# DDR4_SDRAM.net
KiCad netlist of a schematic drawn in Altium Designer
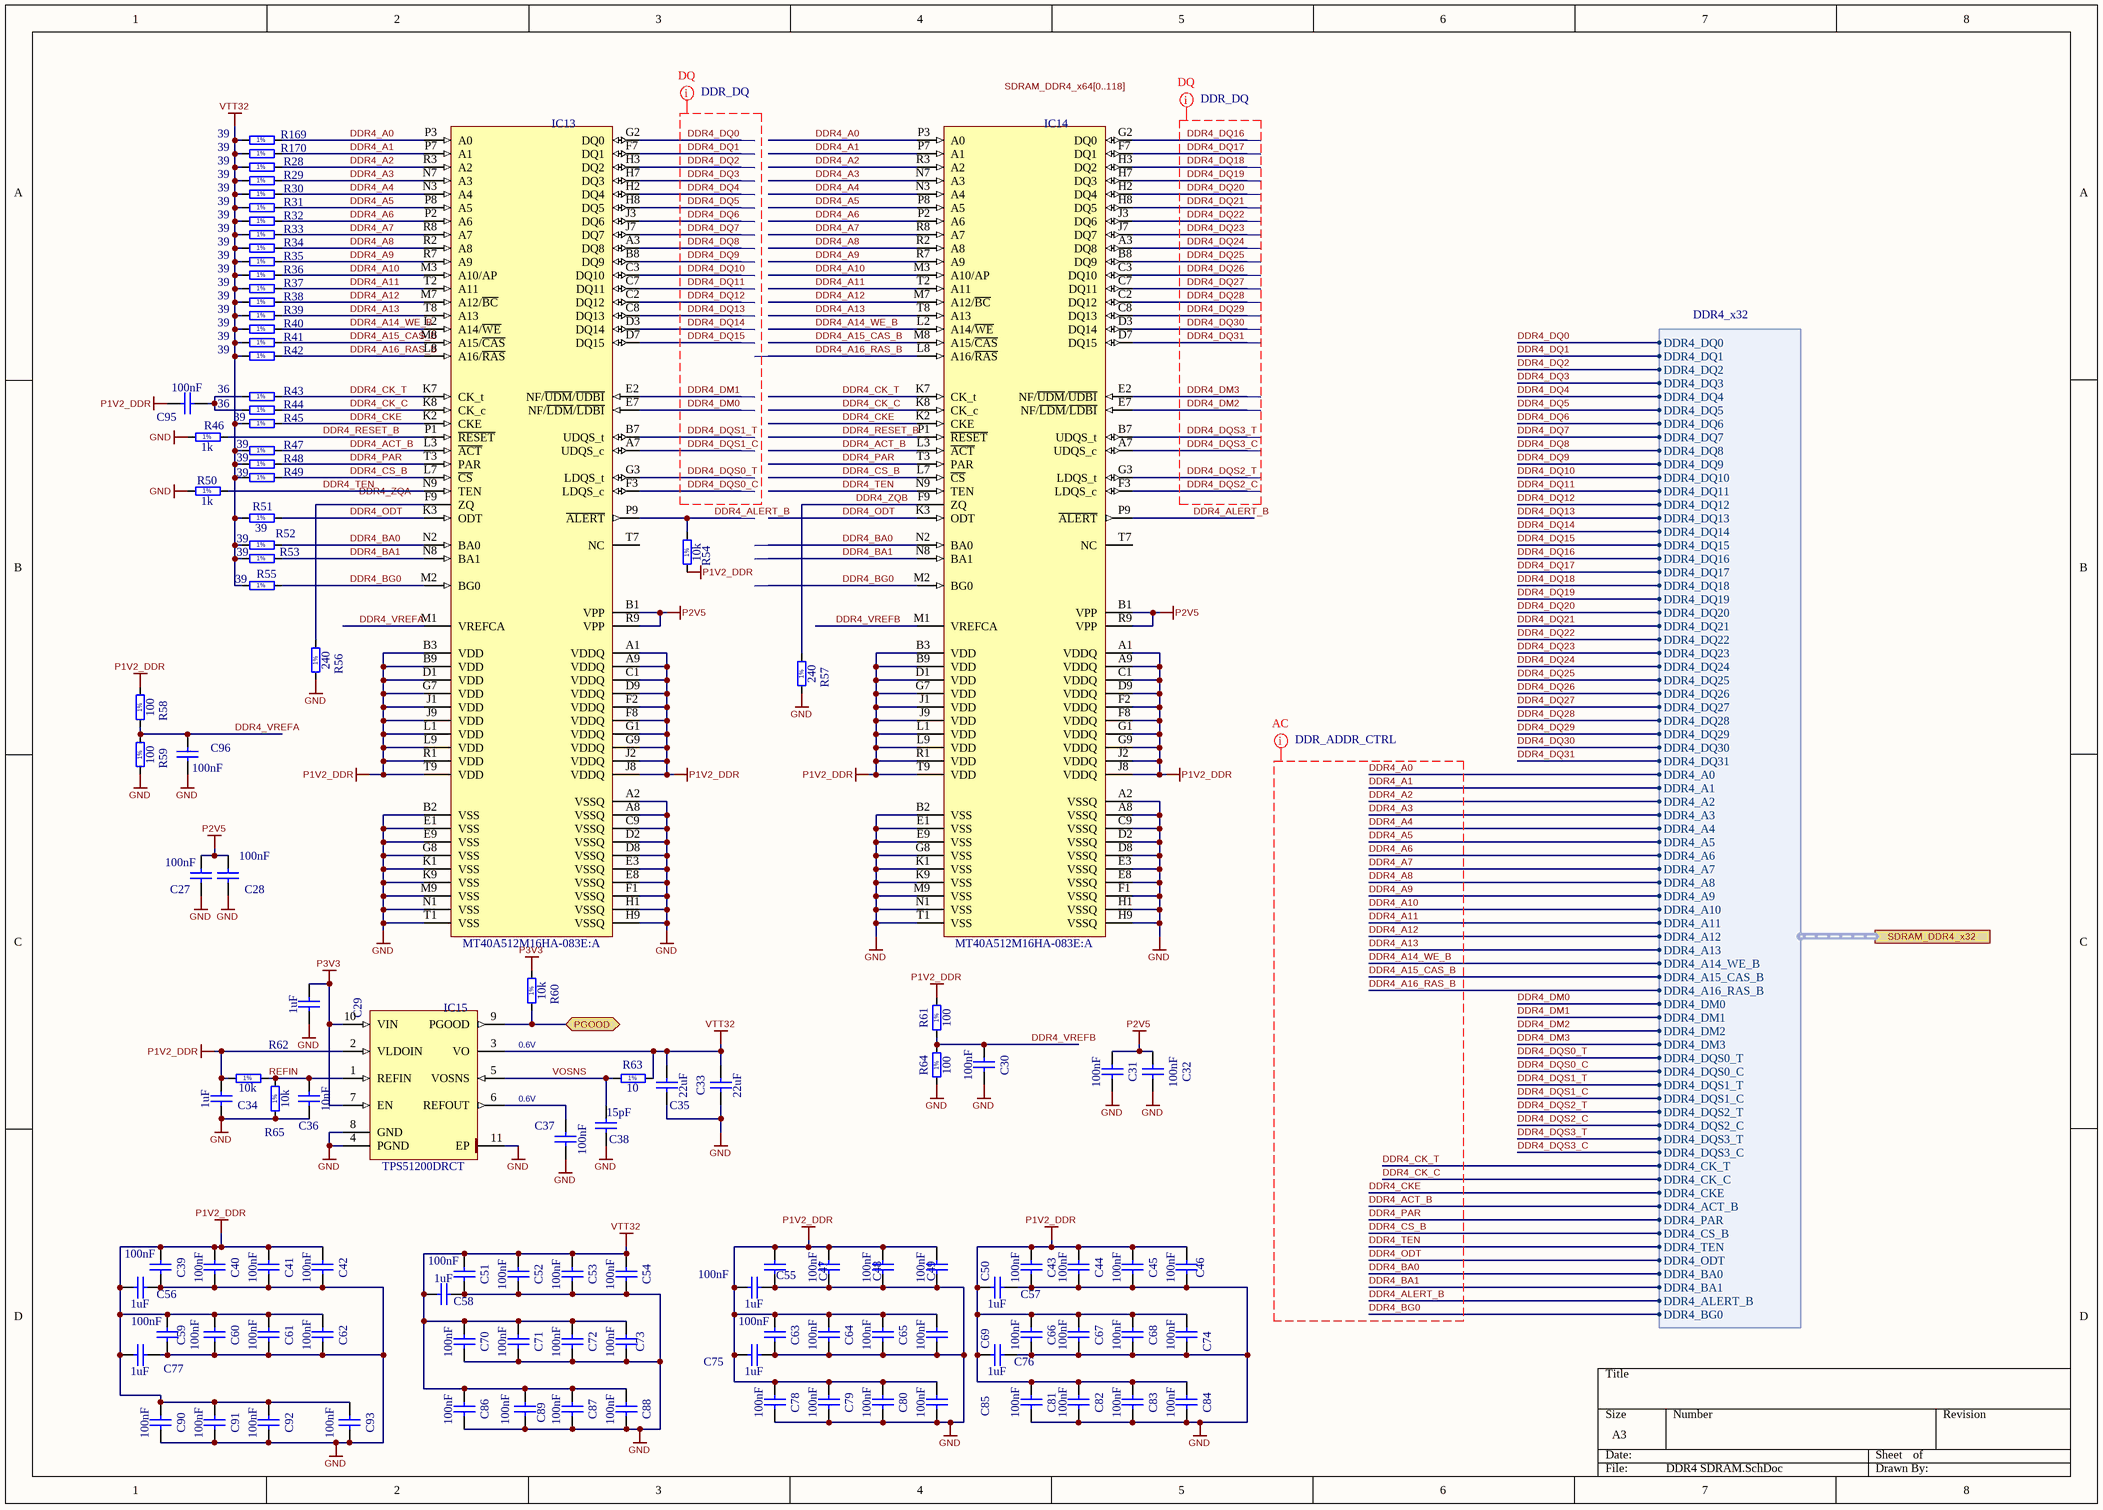
[diagram p0: DDR4 SDRAM.SchDoc]

(export (version "E")
  (design (tool "Eeschema 10.0.6"))
  (components
    (comp (ref "C27")
      (value "100nF")
      (footprint "CAPC0603X33N")
      (description "Non-polarised capacitor")
      (fields
        (field (name "MANUFACTURER PART NUMBER") "CC0201_100NF_6.3V_10%_X5R")
        (field (name "MANUFACTURER") "GENERIC")
        (field (name "AUTHOR") "CERN DEM JLC")
      )
      (libsource (lib "Capacitors") (part "Capacitor - non polarized"))
    )
    (comp (ref "C28")
      (value "100nF")
      (footprint "CAPC0603X33N")
      (description "Non-polarised capacitor")
      (fields
        (field (name "MANUFACTURER PART NUMBER") "CC0201_100NF_6.3V_10%_X5R")
        (field (name "MANUFACTURER") "GENERIC")
        (field (name "AUTHOR") "CERN DEM JLC")
      )
      (libsource (lib "Capacitors") (part "Capacitor - non polarized"))
    )
    (comp (ref "C29")
      (value "1uF")
      (footprint "CAPC1005X55N")
      (description "Non-polarised capacitor")
      (fields
        (field (name "MANUFACTURER PART NUMBER") "CC0402_1UF_16V_10%_X5R")
        (field (name "MANUFACTURER") "GENERIC")
        (field (name "AUTHOR") "CERN DEM JLC")
      )
      (libsource (lib "Capacitors") (part "Capacitor - non polarized"))
    )
    (comp (ref "C30")
      (value "100nF")
      (footprint "CAPC0603X33N")
      (description "Non-polarised capacitor")
      (fields
        (field (name "MANUFACTURER PART NUMBER") "CC0201_100NF_6.3V_10%_X5R")
        (field (name "MANUFACTURER") "GENERIC")
        (field (name "AUTHOR") "CERN DEM JLC")
      )
      (libsource (lib "Capacitors") (part "Capacitor - non polarized"))
    )
    (comp (ref "C31")
      (value "100nF")
      (footprint "CAPC0603X33N")
      (description "Non-polarised capacitor")
      (fields
        (field (name "MANUFACTURER PART NUMBER") "CC0201_100NF_6.3V_10%_X5R")
        (field (name "MANUFACTURER") "GENERIC")
        (field (name "AUTHOR") "CERN DEM JLC")
      )
      (libsource (lib "Capacitors") (part "Capacitor - non polarized"))
    )
    (comp (ref "C32")
      (value "100nF")
      (footprint "CAPC0603X33N")
      (description "Non-polarised capacitor")
      (fields
        (field (name "MANUFACTURER PART NUMBER") "CC0201_100NF_6.3V_10%_X5R")
        (field (name "MANUFACTURER") "GENERIC")
        (field (name "AUTHOR") "CERN DEM JLC")
      )
      (libsource (lib "Capacitors") (part "Capacitor - non polarized"))
    )
    (comp (ref "C33")
      (value "22uF")
      (footprint "CAPC2012X135N")
      (description "Non-polarised capacitor")
      (fields
        (field (name "MANUFACTURER PART NUMBER") "CC0805_22UF_10V_+80%-20%_Y5V")
        (field (name "MANUFACTURER") "GENERIC")
        (field (name "AUTHOR") "CERN DEM JLC")
      )
      (libsource (lib "Capacitors") (part "Capacitor - non polarized"))
    )
    (comp (ref "C34")
      (value "1uF")
      (footprint "CAPC1005X55N")
      (description "Non-polarised capacitor")
      (fields
        (field (name "MANUFACTURER PART NUMBER") "CC0402_1UF_16V_10%_X5R")
        (field (name "MANUFACTURER") "GENERIC")
        (field (name "AUTHOR") "CERN DEM JLC")
      )
      (libsource (lib "Capacitors") (part "Capacitor - non polarized"))
    )
    (comp (ref "C35")
      (value "22uF")
      (footprint "CAPC2012X135N")
      (description "Non-polarised capacitor")
      (fields
        (field (name "MANUFACTURER PART NUMBER") "CC0805_22UF_10V_+80%-20%_Y5V")
        (field (name "MANUFACTURER") "GENERIC")
        (field (name "AUTHOR") "CERN DEM JLC")
      )
      (libsource (lib "Capacitors") (part "Capacitor - non polarized"))
    )
    (comp (ref "C36")
      (value "10nF")
      (footprint "CAPC1005X55N")
      (description "Non-polarised capacitor")
      (fields
        (field (name "MANUFACTURER PART NUMBER") "CC0402_10NF_25V_10%_X7R")
        (field (name "MANUFACTURER") "GENERIC")
        (field (name "AUTHOR") "CERN DEM JLC")
      )
      (libsource (lib "Capacitors") (part "Capacitor - non polarized"))
    )
    (comp (ref "C37")
      (value "100nF")
      (footprint "CAPC0603X33N")
      (description "Non-polarised capacitor")
      (fields
        (field (name "MANUFACTURER PART NUMBER") "CC0201_100NF_6.3V_10%_X5R")
        (field (name "MANUFACTURER") "GENERIC")
        (field (name "AUTHOR") "CERN DEM JLC")
      )
      (libsource (lib "Capacitors") (part "Capacitor - non polarized"))
    )
    (comp (ref "C38")
      (value "15pF")
      (footprint "CAPC1005X55N")
      (description "Non-polarised capacitor")
      (fields
        (field (name "MANUFACTURER PART NUMBER") "CC0402_15PF_50V_5%_C0G")
        (field (name "MANUFACTURER") "GENERIC")
        (field (name "AUTHOR") "CERN DEM JLC")
      )
      (libsource (lib "Capacitors") (part "Capacitor - non polarized"))
    )
    (comp (ref "C39")
      (value "100nF")
      (footprint "CAPC0603X33N")
      (description "Non-polarised capacitor")
      (fields
        (field (name "MANUFACTURER PART NUMBER") "CC0201_100NF_6.3V_10%_X5R")
        (field (name "MANUFACTURER") "GENERIC")
        (field (name "AUTHOR") "CERN DEM JLC")
      )
      (libsource (lib "Capacitors") (part "Capacitor - non polarized"))
    )
    (comp (ref "C40")
      (value "100nF")
      (footprint "CAPC0603X33N")
      (description "Non-polarised capacitor")
      (fields
        (field (name "MANUFACTURER PART NUMBER") "CC0201_100NF_6.3V_10%_X5R")
        (field (name "MANUFACTURER") "GENERIC")
        (field (name "AUTHOR") "CERN DEM JLC")
      )
      (libsource (lib "Capacitors") (part "Capacitor - non polarized"))
    )
    (comp (ref "C41")
      (value "100nF")
      (footprint "CAPC0603X33N")
      (description "Non-polarised capacitor")
      (fields
        (field (name "MANUFACTURER PART NUMBER") "CC0201_100NF_6.3V_10%_X5R")
        (field (name "MANUFACTURER") "GENERIC")
        (field (name "AUTHOR") "CERN DEM JLC")
      )
      (libsource (lib "Capacitors") (part "Capacitor - non polarized"))
    )
    (comp (ref "C42")
      (value "100nF")
      (footprint "CAPC0603X33N")
      (description "Non-polarised capacitor")
      (fields
        (field (name "MANUFACTURER PART NUMBER") "CC0201_100NF_6.3V_10%_X5R")
        (field (name "MANUFACTURER") "GENERIC")
        (field (name "AUTHOR") "CERN DEM JLC")
      )
      (libsource (lib "Capacitors") (part "Capacitor - non polarized"))
    )
    (comp (ref "C43")
      (value "100nF")
      (footprint "CAPC0603X33N")
      (description "Non-polarised capacitor")
      (fields
        (field (name "MANUFACTURER PART NUMBER") "CC0201_100NF_6.3V_10%_X5R")
        (field (name "MANUFACTURER") "GENERIC")
        (field (name "AUTHOR") "CERN DEM JLC")
      )
      (libsource (lib "Capacitors") (part "Capacitor - non polarized"))
    )
    (comp (ref "C44")
      (value "100nF")
      (footprint "CAPC0603X33N")
      (description "Non-polarised capacitor")
      (fields
        (field (name "MANUFACTURER PART NUMBER") "CC0201_100NF_6.3V_10%_X5R")
        (field (name "MANUFACTURER") "GENERIC")
        (field (name "AUTHOR") "CERN DEM JLC")
      )
      (libsource (lib "Capacitors") (part "Capacitor - non polarized"))
    )
    (comp (ref "C45")
      (value "100nF")
      (footprint "CAPC0603X33N")
      (description "Non-polarised capacitor")
      (fields
        (field (name "MANUFACTURER PART NUMBER") "CC0201_100NF_6.3V_10%_X5R")
        (field (name "MANUFACTURER") "GENERIC")
        (field (name "AUTHOR") "CERN DEM JLC")
      )
      (libsource (lib "Capacitors") (part "Capacitor - non polarized"))
    )
    (comp (ref "C46")
      (value "100nF")
      (footprint "CAPC0603X33N")
      (description "Non-polarised capacitor")
      (fields
        (field (name "MANUFACTURER PART NUMBER") "CC0201_100NF_6.3V_10%_X5R")
        (field (name "MANUFACTURER") "GENERIC")
        (field (name "AUTHOR") "CERN DEM JLC")
      )
      (libsource (lib "Capacitors") (part "Capacitor - non polarized"))
    )
    (comp (ref "C47")
      (value "100nF")
      (footprint "CAPC0603X33N")
      (description "Non-polarised capacitor")
      (fields
        (field (name "MANUFACTURER PART NUMBER") "CC0201_100NF_6.3V_10%_X5R")
        (field (name "MANUFACTURER") "GENERIC")
        (field (name "AUTHOR") "CERN DEM JLC")
      )
      (libsource (lib "Capacitors") (part "Capacitor - non polarized"))
    )
    (comp (ref "C48")
      (value "100nF")
      (footprint "CAPC0603X33N")
      (description "Non-polarised capacitor")
      (fields
        (field (name "MANUFACTURER PART NUMBER") "CC0201_100NF_6.3V_10%_X5R")
        (field (name "MANUFACTURER") "GENERIC")
        (field (name "AUTHOR") "CERN DEM JLC")
      )
      (libsource (lib "Capacitors") (part "Capacitor - non polarized"))
    )
    (comp (ref "C49")
      (value "100nF")
      (footprint "CAPC0603X33N")
      (description "Non-polarised capacitor")
      (fields
        (field (name "MANUFACTURER PART NUMBER") "CC0201_100NF_6.3V_10%_X5R")
        (field (name "MANUFACTURER") "GENERIC")
        (field (name "AUTHOR") "CERN DEM JLC")
      )
      (libsource (lib "Capacitors") (part "Capacitor - non polarized"))
    )
    (comp (ref "C50")
      (value "100nF")
      (footprint "CAPC0603X33N")
      (description "Non-polarised capacitor")
      (fields
        (field (name "MANUFACTURER PART NUMBER") "CC0201_100NF_6.3V_10%_X5R")
        (field (name "MANUFACTURER") "GENERIC")
        (field (name "AUTHOR") "CERN DEM JLC")
      )
      (libsource (lib "Capacitors") (part "Capacitor - non polarized"))
    )
    (comp (ref "C51")
      (value "100nF")
      (footprint "CAPC0603X33N")
      (description "Non-polarised capacitor")
      (fields
        (field (name "MANUFACTURER PART NUMBER") "CC0201_100NF_6.3V_10%_X5R")
        (field (name "MANUFACTURER") "GENERIC")
        (field (name "AUTHOR") "CERN DEM JLC")
      )
      (libsource (lib "Capacitors") (part "Capacitor - non polarized"))
    )
    (comp (ref "C52")
      (value "100nF")
      (footprint "CAPC0603X33N")
      (description "Non-polarised capacitor")
      (fields
        (field (name "MANUFACTURER PART NUMBER") "CC0201_100NF_6.3V_10%_X5R")
        (field (name "MANUFACTURER") "GENERIC")
        (field (name "AUTHOR") "CERN DEM JLC")
      )
      (libsource (lib "Capacitors") (part "Capacitor - non polarized"))
    )
    (comp (ref "C53")
      (value "100nF")
      (footprint "CAPC0603X33N")
      (description "Non-polarised capacitor")
      (fields
        (field (name "MANUFACTURER PART NUMBER") "CC0201_100NF_6.3V_10%_X5R")
        (field (name "MANUFACTURER") "GENERIC")
        (field (name "AUTHOR") "CERN DEM JLC")
      )
      (libsource (lib "Capacitors") (part "Capacitor - non polarized"))
    )
    (comp (ref "C54")
      (value "100nF")
      (footprint "CAPC0603X33N")
      (description "Non-polarised capacitor")
      (fields
        (field (name "MANUFACTURER PART NUMBER") "CC0201_100NF_6.3V_10%_X5R")
        (field (name "MANUFACTURER") "GENERIC")
        (field (name "AUTHOR") "CERN DEM JLC")
      )
      (libsource (lib "Capacitors") (part "Capacitor - non polarized"))
    )
    (comp (ref "C55")
      (value "1uF")
      (footprint "CAPC1005X55N")
      (description "Non-polarised capacitor")
      (fields
        (field (name "MANUFACTURER PART NUMBER") "CC0402_1UF_16V_10%_X5R")
        (field (name "MANUFACTURER") "GENERIC")
        (field (name "AUTHOR") "CERN DEM JLC")
      )
      (libsource (lib "Capacitors") (part "Capacitor - non polarized"))
    )
    (comp (ref "C56")
      (value "1uF")
      (footprint "CAPC1005X55N")
      (description "Non-polarised capacitor")
      (fields
        (field (name "MANUFACTURER PART NUMBER") "CC0402_1UF_16V_10%_X5R")
        (field (name "MANUFACTURER") "GENERIC")
        (field (name "AUTHOR") "CERN DEM JLC")
      )
      (libsource (lib "Capacitors") (part "Capacitor - non polarized"))
    )
    (comp (ref "C57")
      (value "1uF")
      (footprint "CAPC1005X55N")
      (description "Non-polarised capacitor")
      (fields
        (field (name "MANUFACTURER PART NUMBER") "CC0402_1UF_16V_10%_X5R")
        (field (name "MANUFACTURER") "GENERIC")
        (field (name "AUTHOR") "CERN DEM JLC")
      )
      (libsource (lib "Capacitors") (part "Capacitor - non polarized"))
    )
    (comp (ref "C58")
      (value "1uF")
      (footprint "CAPC1005X55N")
      (description "Non-polarised capacitor")
      (fields
        (field (name "MANUFACTURER PART NUMBER") "CC0402_1UF_16V_10%_X5R")
        (field (name "MANUFACTURER") "GENERIC")
        (field (name "AUTHOR") "CERN DEM JLC")
      )
      (libsource (lib "Capacitors") (part "Capacitor - non polarized"))
    )
    (comp (ref "C59")
      (value "100nF")
      (footprint "CAPC0603X33N")
      (description "Non-polarised capacitor")
      (fields
        (field (name "MANUFACTURER PART NUMBER") "CC0201_100NF_6.3V_10%_X5R")
        (field (name "MANUFACTURER") "GENERIC")
        (field (name "AUTHOR") "CERN DEM JLC")
      )
      (libsource (lib "Capacitors") (part "Capacitor - non polarized"))
    )
    (comp (ref "C60")
      (value "100nF")
      (footprint "CAPC0603X33N")
      (description "Non-polarised capacitor")
      (fields
        (field (name "MANUFACTURER PART NUMBER") "CC0201_100NF_6.3V_10%_X5R")
        (field (name "MANUFACTURER") "GENERIC")
        (field (name "AUTHOR") "CERN DEM JLC")
      )
      (libsource (lib "Capacitors") (part "Capacitor - non polarized"))
    )
    (comp (ref "C61")
      (value "100nF")
      (footprint "CAPC0603X33N")
      (description "Non-polarised capacitor")
      (fields
        (field (name "MANUFACTURER PART NUMBER") "CC0201_100NF_6.3V_10%_X5R")
        (field (name "MANUFACTURER") "GENERIC")
        (field (name "AUTHOR") "CERN DEM JLC")
      )
      (libsource (lib "Capacitors") (part "Capacitor - non polarized"))
    )
    (comp (ref "C62")
      (value "100nF")
      (footprint "CAPC0603X33N")
      (description "Non-polarised capacitor")
      (fields
        (field (name "MANUFACTURER PART NUMBER") "CC0201_100NF_6.3V_10%_X5R")
        (field (name "MANUFACTURER") "GENERIC")
        (field (name "AUTHOR") "CERN DEM JLC")
      )
      (libsource (lib "Capacitors") (part "Capacitor - non polarized"))
    )
    (comp (ref "C63")
      (value "100nF")
      (footprint "CAPC0603X33N")
      (description "Non-polarised capacitor")
      (fields
        (field (name "MANUFACTURER PART NUMBER") "CC0201_100NF_6.3V_10%_X5R")
        (field (name "MANUFACTURER") "GENERIC")
        (field (name "AUTHOR") "CERN DEM JLC")
      )
      (libsource (lib "Capacitors") (part "Capacitor - non polarized"))
    )
    (comp (ref "C64")
      (value "100nF")
      (footprint "CAPC0603X33N")
      (description "Non-polarised capacitor")
      (fields
        (field (name "MANUFACTURER PART NUMBER") "CC0201_100NF_6.3V_10%_X5R")
        (field (name "MANUFACTURER") "GENERIC")
        (field (name "AUTHOR") "CERN DEM JLC")
      )
      (libsource (lib "Capacitors") (part "Capacitor - non polarized"))
    )
    (comp (ref "C65")
      (value "100nF")
      (footprint "CAPC0603X33N")
      (description "Non-polarised capacitor")
      (fields
        (field (name "MANUFACTURER PART NUMBER") "CC0201_100NF_6.3V_10%_X5R")
        (field (name "MANUFACTURER") "GENERIC")
        (field (name "AUTHOR") "CERN DEM JLC")
      )
      (libsource (lib "Capacitors") (part "Capacitor - non polarized"))
    )
    (comp (ref "C66")
      (value "100nF")
      (footprint "CAPC0603X33N")
      (description "Non-polarised capacitor")
      (fields
        (field (name "MANUFACTURER PART NUMBER") "CC0201_100NF_6.3V_10%_X5R")
        (field (name "MANUFACTURER") "GENERIC")
        (field (name "AUTHOR") "CERN DEM JLC")
      )
      (libsource (lib "Capacitors") (part "Capacitor - non polarized"))
    )
    (comp (ref "C67")
      (value "100nF")
      (footprint "CAPC0603X33N")
      (description "Non-polarised capacitor")
      (fields
        (field (name "MANUFACTURER PART NUMBER") "CC0201_100NF_6.3V_10%_X5R")
        (field (name "MANUFACTURER") "GENERIC")
        (field (name "AUTHOR") "CERN DEM JLC")
      )
      (libsource (lib "Capacitors") (part "Capacitor - non polarized"))
    )
    (comp (ref "C68")
      (value "100nF")
      (footprint "CAPC0603X33N")
      (description "Non-polarised capacitor")
      (fields
        (field (name "MANUFACTURER PART NUMBER") "CC0201_100NF_6.3V_10%_X5R")
        (field (name "MANUFACTURER") "GENERIC")
        (field (name "AUTHOR") "CERN DEM JLC")
      )
      (libsource (lib "Capacitors") (part "Capacitor - non polarized"))
    )
    (comp (ref "C69")
      (value "100nF")
      (footprint "CAPC0603X33N")
      (description "Non-polarised capacitor")
      (fields
        (field (name "MANUFACTURER PART NUMBER") "CC0201_100NF_6.3V_10%_X5R")
        (field (name "MANUFACTURER") "GENERIC")
        (field (name "AUTHOR") "CERN DEM JLC")
      )
      (libsource (lib "Capacitors") (part "Capacitor - non polarized"))
    )
    (comp (ref "C70")
      (value "100nF")
      (footprint "CAPC0603X33N")
      (description "Non-polarised capacitor")
      (fields
        (field (name "MANUFACTURER PART NUMBER") "CC0201_100NF_6.3V_10%_X5R")
        (field (name "MANUFACTURER") "GENERIC")
        (field (name "AUTHOR") "CERN DEM JLC")
      )
      (libsource (lib "Capacitors") (part "Capacitor - non polarized"))
    )
    (comp (ref "C71")
      (value "100nF")
      (footprint "CAPC0603X33N")
      (description "Non-polarised capacitor")
      (fields
        (field (name "MANUFACTURER PART NUMBER") "CC0201_100NF_6.3V_10%_X5R")
        (field (name "MANUFACTURER") "GENERIC")
        (field (name "AUTHOR") "CERN DEM JLC")
      )
      (libsource (lib "Capacitors") (part "Capacitor - non polarized"))
    )
    (comp (ref "C72")
      (value "100nF")
      (footprint "CAPC0603X33N")
      (description "Non-polarised capacitor")
      (fields
        (field (name "MANUFACTURER PART NUMBER") "CC0201_100NF_6.3V_10%_X5R")
        (field (name "MANUFACTURER") "GENERIC")
        (field (name "AUTHOR") "CERN DEM JLC")
      )
      (libsource (lib "Capacitors") (part "Capacitor - non polarized"))
    )
    (comp (ref "C73")
      (value "100nF")
      (footprint "CAPC0603X33N")
      (description "Non-polarised capacitor")
      (fields
        (field (name "MANUFACTURER PART NUMBER") "CC0201_100NF_6.3V_10%_X5R")
        (field (name "MANUFACTURER") "GENERIC")
        (field (name "AUTHOR") "CERN DEM JLC")
      )
      (libsource (lib "Capacitors") (part "Capacitor - non polarized"))
    )
    (comp (ref "C74")
      (value "100nF")
      (footprint "CAPC0603X33N")
      (description "Non-polarised capacitor")
      (fields
        (field (name "MANUFACTURER PART NUMBER") "CC0201_100NF_6.3V_10%_X5R")
        (field (name "MANUFACTURER") "GENERIC")
        (field (name "AUTHOR") "CERN DEM JLC")
      )
      (libsource (lib "Capacitors") (part "Capacitor - non polarized"))
    )
    (comp (ref "C75")
      (value "1uF")
      (footprint "CAPC1005X55N")
      (description "Non-polarised capacitor")
      (fields
        (field (name "MANUFACTURER PART NUMBER") "CC0402_1UF_16V_10%_X5R")
        (field (name "MANUFACTURER") "GENERIC")
        (field (name "AUTHOR") "CERN DEM JLC")
      )
      (libsource (lib "Capacitors") (part "Capacitor - non polarized"))
    )
    (comp (ref "C76")
      (value "1uF")
      (footprint "CAPC1005X55N")
      (description "Non-polarised capacitor")
      (fields
        (field (name "MANUFACTURER PART NUMBER") "CC0402_1UF_16V_10%_X5R")
        (field (name "MANUFACTURER") "GENERIC")
        (field (name "AUTHOR") "CERN DEM JLC")
      )
      (libsource (lib "Capacitors") (part "Capacitor - non polarized"))
    )
    (comp (ref "C77")
      (value "1uF")
      (footprint "CAPC1005X55N")
      (description "Non-polarised capacitor")
      (fields
        (field (name "MANUFACTURER PART NUMBER") "CC0402_1UF_16V_10%_X5R")
        (field (name "MANUFACTURER") "GENERIC")
        (field (name "AUTHOR") "CERN DEM JLC")
      )
      (libsource (lib "Capacitors") (part "Capacitor - non polarized"))
    )
    (comp (ref "C78")
      (value "100nF")
      (footprint "CAPC0603X33N")
      (description "Non-polarised capacitor")
      (fields
        (field (name "MANUFACTURER PART NUMBER") "CC0201_100NF_6.3V_10%_X5R")
        (field (name "MANUFACTURER") "GENERIC")
        (field (name "AUTHOR") "CERN DEM JLC")
      )
      (libsource (lib "Capacitors") (part "Capacitor - non polarized"))
    )
    (comp (ref "C79")
      (value "100nF")
      (footprint "CAPC0603X33N")
      (description "Non-polarised capacitor")
      (fields
        (field (name "MANUFACTURER PART NUMBER") "CC0201_100NF_6.3V_10%_X5R")
        (field (name "MANUFACTURER") "GENERIC")
        (field (name "AUTHOR") "CERN DEM JLC")
      )
      (libsource (lib "Capacitors") (part "Capacitor - non polarized"))
    )
    (comp (ref "C80")
      (value "100nF")
      (footprint "CAPC0603X33N")
      (description "Non-polarised capacitor")
      (fields
        (field (name "MANUFACTURER PART NUMBER") "CC0201_100NF_6.3V_10%_X5R")
        (field (name "MANUFACTURER") "GENERIC")
        (field (name "AUTHOR") "CERN DEM JLC")
      )
      (libsource (lib "Capacitors") (part "Capacitor - non polarized"))
    )
    (comp (ref "C81")
      (value "100nF")
      (footprint "CAPC0603X33N")
      (description "Non-polarised capacitor")
      (fields
        (field (name "MANUFACTURER PART NUMBER") "CC0201_100NF_6.3V_10%_X5R")
        (field (name "MANUFACTURER") "GENERIC")
        (field (name "AUTHOR") "CERN DEM JLC")
      )
      (libsource (lib "Capacitors") (part "Capacitor - non polarized"))
    )
    (comp (ref "C82")
      (value "100nF")
      (footprint "CAPC0603X33N")
      (description "Non-polarised capacitor")
      (fields
        (field (name "MANUFACTURER PART NUMBER") "CC0201_100NF_6.3V_10%_X5R")
        (field (name "MANUFACTURER") "GENERIC")
        (field (name "AUTHOR") "CERN DEM JLC")
      )
      (libsource (lib "Capacitors") (part "Capacitor - non polarized"))
    )
    (comp (ref "C83")
      (value "100nF")
      (footprint "CAPC0603X33N")
      (description "Non-polarised capacitor")
      (fields
        (field (name "MANUFACTURER PART NUMBER") "CC0201_100NF_6.3V_10%_X5R")
        (field (name "MANUFACTURER") "GENERIC")
        (field (name "AUTHOR") "CERN DEM JLC")
      )
      (libsource (lib "Capacitors") (part "Capacitor - non polarized"))
    )
    (comp (ref "C84")
      (value "100nF")
      (footprint "CAPC0603X33N")
      (description "Non-polarised capacitor")
      (fields
        (field (name "MANUFACTURER PART NUMBER") "CC0201_100NF_6.3V_10%_X5R")
        (field (name "MANUFACTURER") "GENERIC")
        (field (name "AUTHOR") "CERN DEM JLC")
      )
      (libsource (lib "Capacitors") (part "Capacitor - non polarized"))
    )
    (comp (ref "C85")
      (value "100nF")
      (footprint "CAPC0603X33N")
      (description "Non-polarised capacitor")
      (fields
        (field (name "MANUFACTURER PART NUMBER") "CC0201_100NF_6.3V_10%_X5R")
        (field (name "MANUFACTURER") "GENERIC")
        (field (name "AUTHOR") "CERN DEM JLC")
      )
      (libsource (lib "Capacitors") (part "Capacitor - non polarized"))
    )
    (comp (ref "C86")
      (value "100nF")
      (footprint "CAPC0603X33N")
      (description "Non-polarised capacitor")
      (fields
        (field (name "MANUFACTURER PART NUMBER") "CC0201_100NF_6.3V_10%_X5R")
        (field (name "MANUFACTURER") "GENERIC")
        (field (name "AUTHOR") "CERN DEM JLC")
      )
      (libsource (lib "Capacitors") (part "Capacitor - non polarized"))
    )
    (comp (ref "C87")
      (value "100nF")
      (footprint "CAPC0603X33N")
      (description "Non-polarised capacitor")
      (fields
        (field (name "MANUFACTURER PART NUMBER") "CC0201_100NF_6.3V_10%_X5R")
        (field (name "MANUFACTURER") "GENERIC")
        (field (name "AUTHOR") "CERN DEM JLC")
      )
      (libsource (lib "Capacitors") (part "Capacitor - non polarized"))
    )
    (comp (ref "C88")
      (value "100nF")
      (footprint "CAPC0603X33N")
      (description "Non-polarised capacitor")
      (fields
        (field (name "MANUFACTURER PART NUMBER") "CC0201_100NF_6.3V_10%_X5R")
        (field (name "MANUFACTURER") "GENERIC")
        (field (name "AUTHOR") "CERN DEM JLC")
      )
      (libsource (lib "Capacitors") (part "Capacitor - non polarized"))
    )
    (comp (ref "C89")
      (value "100nF")
      (footprint "CAPC0603X33N")
      (description "Non-polarised capacitor")
      (fields
        (field (name "MANUFACTURER PART NUMBER") "CC0201_100NF_6.3V_10%_X5R")
        (field (name "MANUFACTURER") "GENERIC")
        (field (name "AUTHOR") "CERN DEM JLC")
      )
      (libsource (lib "Capacitors") (part "Capacitor - non polarized"))
    )
    (comp (ref "C90")
      (value "100nF")
      (footprint "CAPC0603X33N")
      (description "Non-polarised capacitor")
      (fields
        (field (name "MANUFACTURER PART NUMBER") "CC0201_100NF_6.3V_10%_X5R")
        (field (name "MANUFACTURER") "GENERIC")
        (field (name "AUTHOR") "CERN DEM JLC")
      )
      (libsource (lib "Capacitors") (part "Capacitor - non polarized"))
    )
    (comp (ref "C91")
      (value "100nF")
      (footprint "CAPC0603X33N")
      (description "Non-polarised capacitor")
      (fields
        (field (name "MANUFACTURER PART NUMBER") "CC0201_100NF_6.3V_10%_X5R")
        (field (name "MANUFACTURER") "GENERIC")
        (field (name "AUTHOR") "CERN DEM JLC")
      )
      (libsource (lib "Capacitors") (part "Capacitor - non polarized"))
    )
    (comp (ref "C92")
      (value "100nF")
      (footprint "CAPC0603X33N")
      (description "Non-polarised capacitor")
      (fields
        (field (name "MANUFACTURER PART NUMBER") "CC0201_100NF_6.3V_10%_X5R")
        (field (name "MANUFACTURER") "GENERIC")
        (field (name "AUTHOR") "CERN DEM JLC")
      )
      (libsource (lib "Capacitors") (part "Capacitor - non polarized"))
    )
    (comp (ref "C93")
      (value "100nF")
      (footprint "CAPC0603X33N")
      (description "Non-polarised capacitor")
      (fields
        (field (name "MANUFACTURER PART NUMBER") "CC0201_100NF_6.3V_10%_X5R")
        (field (name "MANUFACTURER") "GENERIC")
        (field (name "AUTHOR") "CERN DEM JLC")
      )
      (libsource (lib "Capacitors") (part "Capacitor - non polarized"))
    )
    (comp (ref "C95")
      (value "100nF")
      (footprint "CAPC0603X33N")
      (description "Non-polarised capacitor")
      (fields
        (field (name "MANUFACTURER PART NUMBER") "CC0201_100NF_6.3V_10%_X5R")
        (field (name "MANUFACTURER") "GENERIC")
        (field (name "AUTHOR") "CERN DEM JLC")
      )
      (libsource (lib "Capacitors") (part "Capacitor - non polarized"))
    )
    (comp (ref "C96")
      (value "100nF")
      (footprint "CAPC0603X33N")
      (description "Non-polarised capacitor")
      (fields
        (field (name "MANUFACTURER PART NUMBER") "CC0201_100NF_6.3V_10%_X5R")
        (field (name "MANUFACTURER") "GENERIC")
        (field (name "AUTHOR") "CERN DEM JLC")
      )
      (libsource (lib "Capacitors") (part "Capacitor - non polarized"))
    )
    (comp (ref "IC13")
      (value "MT40A512M16HA-083E:A")
      (footprint "BGA96C80P9X16_900X1400X120")
      (description "+1.2V, 8Gb (512 Meg x 16 x 8 Banks) DDR4 SDRAM")
      (fields (field (name "MANUFACTURER") "MICRON TECHNOLOGY") (field (name "AUTHOR") "CERN DEM MR"))
      (libsource (lib "ICs And Semiconductors") (part "MT40A512M16HA"))
    )
    (comp (ref "IC14")
      (value "MT40A512M16HA-083E:A")
      (footprint "BGA96C80P9X16_900X1400X120")
      (description "+1.2V, 8Gb (512 Meg x 16 x 8 Banks) DDR4 SDRAM")
      (fields (field (name "MANUFACTURER") "MICRON TECHNOLOGY") (field (name "AUTHOR") "CERN DEM MR"))
      (libsource (lib "ICs And Semiconductors") (part "MT40A512M16HA"))
    )
    (comp (ref "IC15")
      (value "TPS51200DRCT")
      (footprint "TEXAS_DRC (S-PVSON-N10)")
      (description "Sink/Source DDR Termination Regulator")
      (fields (field (name "MANUFACTURER") "TEXAS INSTRUMENTS") (field (name "AUTHOR") "CERN DEM JLC"))
      (libsource (lib "ICs And Semiconductors") (part "TPS51200DRC"))
    )
    (comp (ref "R28")
      (value "39")
      (footprint "RESC1005X40N")
      (description "Resistor - 1%")
      (fields
        (field (name "MANUFACTURER PART NUMBER") "R0402_39R_1%_0.0625W_100PPM")
        (field (name "MANUFACTURER") "GENERIC")
        (field (name "AUTHOR") "CERN DEM JLC")
      )
      (libsource (lib "Resistors") (part "Resistor - 1%"))
    )
    (comp (ref "R29")
      (value "39")
      (footprint "RESC1005X40N")
      (description "Resistor - 1%")
      (fields
        (field (name "MANUFACTURER PART NUMBER") "R0402_39R_1%_0.0625W_100PPM")
        (field (name "MANUFACTURER") "GENERIC")
        (field (name "AUTHOR") "CERN DEM JLC")
      )
      (libsource (lib "Resistors") (part "Resistor - 1%"))
    )
    (comp (ref "R30")
      (value "39")
      (footprint "RESC1005X40N")
      (description "Resistor - 1%")
      (fields
        (field (name "MANUFACTURER PART NUMBER") "R0402_39R_1%_0.0625W_100PPM")
        (field (name "MANUFACTURER") "GENERIC")
        (field (name "AUTHOR") "CERN DEM JLC")
      )
      (libsource (lib "Resistors") (part "Resistor - 1%"))
    )
    (comp (ref "R31")
      (value "39")
      (footprint "RESC1005X40N")
      (description "Resistor - 1%")
      (fields
        (field (name "MANUFACTURER PART NUMBER") "R0402_39R_1%_0.0625W_100PPM")
        (field (name "MANUFACTURER") "GENERIC")
        (field (name "AUTHOR") "CERN DEM JLC")
      )
      (libsource (lib "Resistors") (part "Resistor - 1%"))
    )
    (comp (ref "R32")
      (value "39")
      (footprint "RESC1005X40N")
      (description "Resistor - 1%")
      (fields
        (field (name "MANUFACTURER PART NUMBER") "R0402_39R_1%_0.0625W_100PPM")
        (field (name "MANUFACTURER") "GENERIC")
        (field (name "AUTHOR") "CERN DEM JLC")
      )
      (libsource (lib "Resistors") (part "Resistor - 1%"))
    )
    (comp (ref "R33")
      (value "39")
      (footprint "RESC1005X40N")
      (description "Resistor - 1%")
      (fields
        (field (name "MANUFACTURER PART NUMBER") "R0402_39R_1%_0.0625W_100PPM")
        (field (name "MANUFACTURER") "GENERIC")
        (field (name "AUTHOR") "CERN DEM JLC")
      )
      (libsource (lib "Resistors") (part "Resistor - 1%"))
    )
    (comp (ref "R34")
      (value "39")
      (footprint "RESC1005X40N")
      (description "Resistor - 1%")
      (fields
        (field (name "MANUFACTURER PART NUMBER") "R0402_39R_1%_0.0625W_100PPM")
        (field (name "MANUFACTURER") "GENERIC")
        (field (name "AUTHOR") "CERN DEM JLC")
      )
      (libsource (lib "Resistors") (part "Resistor - 1%"))
    )
    (comp (ref "R35")
      (value "39")
      (footprint "RESC1005X40N")
      (description "Resistor - 1%")
      (fields
        (field (name "MANUFACTURER PART NUMBER") "R0402_39R_1%_0.0625W_100PPM")
        (field (name "MANUFACTURER") "GENERIC")
        (field (name "AUTHOR") "CERN DEM JLC")
      )
      (libsource (lib "Resistors") (part "Resistor - 1%"))
    )
    (comp (ref "R36")
      (value "39")
      (footprint "RESC1005X40N")
      (description "Resistor - 1%")
      (fields
        (field (name "MANUFACTURER PART NUMBER") "R0402_39R_1%_0.0625W_100PPM")
        (field (name "MANUFACTURER") "GENERIC")
        (field (name "AUTHOR") "CERN DEM JLC")
      )
      (libsource (lib "Resistors") (part "Resistor - 1%"))
    )
    (comp (ref "R37")
      (value "39")
      (footprint "RESC1005X40N")
      (description "Resistor - 1%")
      (fields
        (field (name "MANUFACTURER PART NUMBER") "R0402_39R_1%_0.0625W_100PPM")
        (field (name "MANUFACTURER") "GENERIC")
        (field (name "AUTHOR") "CERN DEM JLC")
      )
      (libsource (lib "Resistors") (part "Resistor - 1%"))
    )
    (comp (ref "R38")
      (value "39")
      (footprint "RESC1005X40N")
      (description "Resistor - 1%")
      (fields
        (field (name "MANUFACTURER PART NUMBER") "R0402_39R_1%_0.0625W_100PPM")
        (field (name "MANUFACTURER") "GENERIC")
        (field (name "AUTHOR") "CERN DEM JLC")
      )
      (libsource (lib "Resistors") (part "Resistor - 1%"))
    )
    (comp (ref "R39")
      (value "39")
      (footprint "RESC1005X40N")
      (description "Resistor - 1%")
      (fields
        (field (name "MANUFACTURER PART NUMBER") "R0402_39R_1%_0.0625W_100PPM")
        (field (name "MANUFACTURER") "GENERIC")
        (field (name "AUTHOR") "CERN DEM JLC")
      )
      (libsource (lib "Resistors") (part "Resistor - 1%"))
    )
    (comp (ref "R40")
      (value "39")
      (footprint "RESC1005X40N")
      (description "Resistor - 1%")
      (fields
        (field (name "MANUFACTURER PART NUMBER") "R0402_39R_1%_0.0625W_100PPM")
        (field (name "MANUFACTURER") "GENERIC")
        (field (name "AUTHOR") "CERN DEM JLC")
      )
      (libsource (lib "Resistors") (part "Resistor - 1%"))
    )
    (comp (ref "R41")
      (value "39")
      (footprint "RESC1005X40N")
      (description "Resistor - 1%")
      (fields
        (field (name "MANUFACTURER PART NUMBER") "R0402_39R_1%_0.0625W_100PPM")
        (field (name "MANUFACTURER") "GENERIC")
        (field (name "AUTHOR") "CERN DEM JLC")
      )
      (libsource (lib "Resistors") (part "Resistor - 1%"))
    )
    (comp (ref "R42")
      (value "39")
      (footprint "RESC1005X40N")
      (description "Resistor - 1%")
      (fields
        (field (name "MANUFACTURER PART NUMBER") "R0402_39R_1%_0.0625W_100PPM")
        (field (name "MANUFACTURER") "GENERIC")
        (field (name "AUTHOR") "CERN DEM JLC")
      )
      (libsource (lib "Resistors") (part "Resistor - 1%"))
    )
    (comp (ref "R43")
      (value "36")
      (footprint "RESC1005X40N")
      (description "Resistor - 1%")
      (fields
        (field (name "MANUFACTURER PART NUMBER") "R0402_36R_1%_0.0625W_100PPM")
        (field (name "MANUFACTURER") "GENERIC")
        (field (name "AUTHOR") "CERN DEM JLC")
      )
      (libsource (lib "Resistors") (part "Resistor - 1%"))
    )
    (comp (ref "R44")
      (value "36")
      (footprint "RESC1005X40N")
      (description "Resistor - 1%")
      (fields
        (field (name "MANUFACTURER PART NUMBER") "R0402_36R_1%_0.0625W_100PPM")
        (field (name "MANUFACTURER") "GENERIC")
        (field (name "AUTHOR") "CERN DEM JLC")
      )
      (libsource (lib "Resistors") (part "Resistor - 1%"))
    )
    (comp (ref "R45")
      (value "39")
      (footprint "RESC1005X40N")
      (description "Resistor - 1%")
      (fields
        (field (name "MANUFACTURER PART NUMBER") "R0402_39R_1%_0.0625W_100PPM")
        (field (name "MANUFACTURER") "GENERIC")
        (field (name "AUTHOR") "CERN DEM JLC")
      )
      (libsource (lib "Resistors") (part "Resistor - 1%"))
    )
    (comp (ref "R46")
      (value "1k")
      (footprint "RESC1005X40N")
      (description "Resistor - 1%")
      (fields
        (field (name "MANUFACTURER PART NUMBER") "R0402_1K_1%_0.0625W_100PPM")
        (field (name "MANUFACTURER") "GENERIC")
        (field (name "AUTHOR") "CERN DEM JLC")
      )
      (libsource (lib "Resistors") (part "Resistor - 1%"))
    )
    (comp (ref "R47")
      (value "39")
      (footprint "RESC1005X40N")
      (description "Resistor - 1%")
      (fields
        (field (name "MANUFACTURER PART NUMBER") "R0402_39R_1%_0.0625W_100PPM")
        (field (name "MANUFACTURER") "GENERIC")
        (field (name "AUTHOR") "CERN DEM JLC")
      )
      (libsource (lib "Resistors") (part "Resistor - 1%"))
    )
    (comp (ref "R48")
      (value "39")
      (footprint "RESC1005X40N")
      (description "Resistor - 1%")
      (fields
        (field (name "MANUFACTURER PART NUMBER") "R0402_39R_1%_0.0625W_100PPM")
        (field (name "MANUFACTURER") "GENERIC")
        (field (name "AUTHOR") "CERN DEM JLC")
      )
      (libsource (lib "Resistors") (part "Resistor - 1%"))
    )
    (comp (ref "R49")
      (value "39")
      (footprint "RESC1005X40N")
      (description "Resistor - 1%")
      (fields
        (field (name "MANUFACTURER PART NUMBER") "R0402_39R_1%_0.0625W_100PPM")
        (field (name "MANUFACTURER") "GENERIC")
        (field (name "AUTHOR") "CERN DEM JLC")
      )
      (libsource (lib "Resistors") (part "Resistor - 1%"))
    )
    (comp (ref "R50")
      (value "1k")
      (footprint "RESC1005X40N")
      (description "Resistor - 1%")
      (fields
        (field (name "MANUFACTURER PART NUMBER") "R0402_1K_1%_0.0625W_100PPM")
        (field (name "MANUFACTURER") "GENERIC")
        (field (name "AUTHOR") "CERN DEM JLC")
      )
      (libsource (lib "Resistors") (part "Resistor - 1%"))
    )
    (comp (ref "R51")
      (value "39")
      (footprint "RESC1005X40N")
      (description "Resistor - 1%")
      (fields
        (field (name "MANUFACTURER PART NUMBER") "R0402_39R_1%_0.0625W_100PPM")
        (field (name "MANUFACTURER") "GENERIC")
        (field (name "AUTHOR") "CERN DEM JLC")
      )
      (libsource (lib "Resistors") (part "Resistor - 1%"))
    )
    (comp (ref "R52")
      (value "39")
      (footprint "RESC1005X40N")
      (description "Resistor - 1%")
      (fields
        (field (name "MANUFACTURER PART NUMBER") "R0402_39R_1%_0.0625W_100PPM")
        (field (name "MANUFACTURER") "GENERIC")
        (field (name "AUTHOR") "CERN DEM JLC")
      )
      (libsource (lib "Resistors") (part "Resistor - 1%"))
    )
    (comp (ref "R53")
      (value "39")
      (footprint "RESC1005X40N")
      (description "Resistor - 1%")
      (fields
        (field (name "MANUFACTURER PART NUMBER") "R0402_39R_1%_0.0625W_100PPM")
        (field (name "MANUFACTURER") "GENERIC")
        (field (name "AUTHOR") "CERN DEM JLC")
      )
      (libsource (lib "Resistors") (part "Resistor - 1%"))
    )
    (comp (ref "R54")
      (value "10k")
      (footprint "RESC1005X40N")
      (description "Resistor - 1%")
      (fields
        (field (name "MANUFACTURER PART NUMBER") "R0402_10K_1%_0.0625W_100PPM")
        (field (name "MANUFACTURER") "GENERIC")
        (field (name "AUTHOR") "CERN DEM JLC")
      )
      (libsource (lib "Resistors") (part "Resistor - 1%"))
    )
    (comp (ref "R55")
      (value "39")
      (footprint "RESC1005X40N")
      (description "Resistor - 1%")
      (fields
        (field (name "MANUFACTURER PART NUMBER") "R0402_39R_1%_0.0625W_100PPM")
        (field (name "MANUFACTURER") "GENERIC")
        (field (name "AUTHOR") "CERN DEM JLC")
      )
      (libsource (lib "Resistors") (part "Resistor - 1%"))
    )
    (comp (ref "R56")
      (value "240")
      (footprint "RESC1005X40N")
      (description "Resistor - 1%")
      (fields
        (field (name "MANUFACTURER PART NUMBER") "R0402_240R_1%_0.0625W_100PPM")
        (field (name "MANUFACTURER") "GENERIC")
        (field (name "AUTHOR") "CERN DEM JLC")
      )
      (libsource (lib "Resistors") (part "Resistor - 1%"))
    )
    (comp (ref "R57")
      (value "240")
      (footprint "RESC1005X40N")
      (description "Resistor - 1%")
      (fields
        (field (name "MANUFACTURER PART NUMBER") "R0402_240R_1%_0.0625W_100PPM")
        (field (name "MANUFACTURER") "GENERIC")
        (field (name "AUTHOR") "CERN DEM JLC")
      )
      (libsource (lib "Resistors") (part "Resistor - 1%"))
    )
    (comp (ref "R58")
      (value "100")
      (footprint "RESC1005X40N")
      (description "Resistor - 1%")
      (fields
        (field (name "MANUFACTURER PART NUMBER") "R0402_100R_1%_0.0625W_100PPM")
        (field (name "MANUFACTURER") "GENERIC")
        (field (name "AUTHOR") "CERN DEM JLC")
      )
      (libsource (lib "Resistors") (part "Resistor - 1%"))
    )
    (comp (ref "R59")
      (value "100")
      (footprint "RESC1005X40N")
      (description "Resistor - 1%")
      (fields
        (field (name "MANUFACTURER PART NUMBER") "R0402_100R_1%_0.0625W_100PPM")
        (field (name "MANUFACTURER") "GENERIC")
        (field (name "AUTHOR") "CERN DEM JLC")
      )
      (libsource (lib "Resistors") (part "Resistor - 1%"))
    )
    (comp (ref "R60")
      (value "10k")
      (footprint "RESC1005X40N")
      (description "Resistor - 1%")
      (fields
        (field (name "MANUFACTURER PART NUMBER") "R0402_10K_1%_0.0625W_100PPM")
        (field (name "MANUFACTURER") "GENERIC")
        (field (name "AUTHOR") "CERN DEM JLC")
      )
      (libsource (lib "Resistors") (part "Resistor - 1%"))
    )
    (comp (ref "R61")
      (value "100")
      (footprint "RESC1005X40N")
      (description "Resistor - 1%")
      (fields
        (field (name "MANUFACTURER PART NUMBER") "R0402_100R_1%_0.0625W_100PPM")
        (field (name "MANUFACTURER") "GENERIC")
        (field (name "AUTHOR") "CERN DEM JLC")
      )
      (libsource (lib "Resistors") (part "Resistor - 1%"))
    )
    (comp (ref "R62")
      (value "10k")
      (footprint "RESC1005X40N")
      (description "Resistor - 1%")
      (fields
        (field (name "MANUFACTURER PART NUMBER") "R0402_10K_1%_0.0625W_100PPM")
        (field (name "MANUFACTURER") "GENERIC")
        (field (name "AUTHOR") "CERN DEM JLC")
      )
      (libsource (lib "Resistors") (part "Resistor - 1%"))
    )
    (comp (ref "R63")
      (value "10")
      (footprint "RESC1005X40N")
      (description "Resistor - 1%")
      (fields
        (field (name "MANUFACTURER PART NUMBER") "R0402_10R_1%_0.0625W_200PPM")
        (field (name "MANUFACTURER") "GENERIC")
        (field (name "AUTHOR") "CERN DEM JLC")
      )
      (libsource (lib "Resistors") (part "Resistor - 1%"))
    )
    (comp (ref "R64")
      (value "100")
      (footprint "RESC1005X40N")
      (description "Resistor - 1%")
      (fields
        (field (name "MANUFACTURER PART NUMBER") "R0402_100R_1%_0.0625W_100PPM")
        (field (name "MANUFACTURER") "GENERIC")
        (field (name "AUTHOR") "CERN DEM JLC")
      )
      (libsource (lib "Resistors") (part "Resistor - 1%"))
    )
    (comp (ref "R65")
      (value "10k")
      (footprint "RESC1005X40N")
      (description "Resistor - 1%")
      (fields
        (field (name "MANUFACTURER PART NUMBER") "R0402_10K_1%_0.0625W_100PPM")
        (field (name "MANUFACTURER") "GENERIC")
        (field (name "AUTHOR") "CERN DEM JLC")
      )
      (libsource (lib "Resistors") (part "Resistor - 1%"))
    )
    (comp (ref "R169")
      (value "39")
      (footprint "RESC1005X40N")
      (description "Resistor - 1%")
      (fields
        (field (name "MANUFACTURER PART NUMBER") "R0402_39R_1%_0.0625W_100PPM")
        (field (name "MANUFACTURER") "GENERIC")
        (field (name "AUTHOR") "CERN DEM JLC")
      )
      (libsource (lib "Resistors") (part "Resistor - 1%"))
    )
    (comp (ref "R170")
      (value "39")
      (footprint "RESC1005X40N")
      (description "Resistor - 1%")
      (fields
        (field (name "MANUFACTURER PART NUMBER") "R0402_39R_1%_0.0625W_100PPM")
        (field (name "MANUFACTURER") "GENERIC")
        (field (name "AUTHOR") "CERN DEM JLC")
      )
      (libsource (lib "Resistors") (part "Resistor - 1%"))
    )
  )
  (nets
    (net (code "121") (name "/DDR4_A0") (class "Default")
      (node (ref "IC13") (pin "P3") (pinfunction "A0_P3") (pintype "input"))
      (node (ref "IC14") (pin "P3") (pinfunction "A0_P3") (pintype "input"))
      (node (ref "R169") (pin "2") (pinfunction "2_2") (pintype "passive"))
    )
    (net (code "122") (name "/DDR4_A1") (class "Default")
      (node (ref "IC13") (pin "P7") (pinfunction "A1_P7") (pintype "input"))
      (node (ref "IC14") (pin "P7") (pinfunction "A1_P7") (pintype "input"))
      (node (ref "R170") (pin "2") (pinfunction "2_2") (pintype "passive"))
    )
    (net (code "123") (name "/DDR4_A2") (class "Default")
      (node (ref "IC13") (pin "R3") (pinfunction "A2_R3") (pintype "input"))
      (node (ref "IC14") (pin "R3") (pinfunction "A2_R3") (pintype "input"))
      (node (ref "R28") (pin "2") (pinfunction "2_2") (pintype "passive"))
    )
    (net (code "124") (name "/DDR4_A3") (class "Default")
      (node (ref "IC13") (pin "N7") (pinfunction "A3_N7") (pintype "input"))
      (node (ref "IC14") (pin "N7") (pinfunction "A3_N7") (pintype "input"))
      (node (ref "R29") (pin "2") (pinfunction "2_2") (pintype "passive"))
    )
    (net (code "125") (name "/DDR4_A4") (class "Default")
      (node (ref "IC13") (pin "N3") (pinfunction "A4_N3") (pintype "input"))
      (node (ref "IC14") (pin "N3") (pinfunction "A4_N3") (pintype "input"))
      (node (ref "R30") (pin "2") (pinfunction "2_2") (pintype "passive"))
    )
    (net (code "126") (name "/DDR4_A5") (class "Default")
      (node (ref "IC13") (pin "P8") (pinfunction "A5_P8") (pintype "input"))
      (node (ref "IC14") (pin "P8") (pinfunction "A5_P8") (pintype "input"))
      (node (ref "R31") (pin "2") (pinfunction "2_2") (pintype "passive"))
    )
    (net (code "127") (name "/DDR4_A6") (class "Default")
      (node (ref "IC13") (pin "P2") (pinfunction "A6_P2") (pintype "input"))
      (node (ref "IC14") (pin "P2") (pinfunction "A6_P2") (pintype "input"))
      (node (ref "R32") (pin "2") (pinfunction "2_2") (pintype "passive"))
    )
    (net (code "128") (name "/DDR4_A7") (class "Default")
      (node (ref "IC13") (pin "R8") (pinfunction "A7_R8") (pintype "input"))
      (node (ref "IC14") (pin "R8") (pinfunction "A7_R8") (pintype "input"))
      (node (ref "R33") (pin "2") (pinfunction "2_2") (pintype "passive"))
    )
    (net (code "129") (name "/DDR4_A8") (class "Default")
      (node (ref "IC13") (pin "R2") (pinfunction "A8_R2") (pintype "input"))
      (node (ref "IC14") (pin "R2") (pinfunction "A8_R2") (pintype "input"))
      (node (ref "R34") (pin "2") (pinfunction "2_2") (pintype "passive"))
    )
    (net (code "130") (name "/DDR4_A9") (class "Default")
      (node (ref "IC13") (pin "R7") (pinfunction "A9_R7") (pintype "input"))
      (node (ref "IC14") (pin "R7") (pinfunction "A9_R7") (pintype "input"))
      (node (ref "R35") (pin "2") (pinfunction "2_2") (pintype "passive"))
    )
    (net (code "131") (name "/DDR4_A10") (class "Default")
      (node (ref "IC13") (pin "M3") (pinfunction "A10/AP_M3") (pintype "input"))
      (node (ref "IC14") (pin "M3") (pinfunction "A10/AP_M3") (pintype "input"))
      (node (ref "R36") (pin "2") (pinfunction "2_2") (pintype "passive"))
    )
    (net (code "132") (name "/DDR4_A11") (class "Default")
      (node (ref "IC13") (pin "T2") (pinfunction "A11_T2") (pintype "input"))
      (node (ref "IC14") (pin "T2") (pinfunction "A11_T2") (pintype "input"))
      (node (ref "R37") (pin "2") (pinfunction "2_2") (pintype "passive"))
    )
    (net (code "133") (name "/DDR4_A12") (class "Default")
      (node (ref "IC13") (pin "M7") (pinfunction "A12/~{BC}_M7") (pintype "input"))
      (node (ref "IC14") (pin "M7") (pinfunction "A12/~{BC}_M7") (pintype "input"))
      (node (ref "R38") (pin "2") (pinfunction "2_2") (pintype "passive"))
    )
    (net (code "134") (name "/DDR4_A13") (class "Default")
      (node (ref "IC13") (pin "T8") (pinfunction "A13_T8") (pintype "input"))
      (node (ref "IC14") (pin "T8") (pinfunction "A13_T8") (pintype "input"))
      (node (ref "R39") (pin "2") (pinfunction "2_2") (pintype "passive"))
    )
    (net (code "135") (name "/DDR4_A14_WE_B") (class "Default")
      (node (ref "IC13") (pin "L2") (pinfunction "A14/~{WE}_L2") (pintype "input"))
      (node (ref "IC14") (pin "L2") (pinfunction "A14/~{WE}_L2") (pintype "input"))
      (node (ref "R40") (pin "2") (pinfunction "2_2") (pintype "passive"))
    )
    (net (code "136") (name "/DDR4_A15_CAS_B") (class "Default")
      (node (ref "IC13") (pin "M8") (pinfunction "A15/~{CAS}_M8") (pintype "input"))
      (node (ref "IC14") (pin "M8") (pinfunction "A15/~{CAS}_M8") (pintype "input"))
      (node (ref "R41") (pin "2") (pinfunction "2_2") (pintype "passive"))
    )
    (net (code "137") (name "/DDR4_A16_RAS_B") (class "Default")
      (node (ref "IC13") (pin "L8") (pinfunction "A16/~{RAS}_L8") (pintype "input"))
      (node (ref "IC14") (pin "L8") (pinfunction "A16/~{RAS}_L8") (pintype "input"))
      (node (ref "R42") (pin "2") (pinfunction "2_2") (pintype "passive"))
    )
    (net (code "138") (name "/DDR4_ACT_B") (class "Default")
      (node (ref "IC13") (pin "L3") (pinfunction "~{ACT}_L3") (pintype "input"))
      (node (ref "IC14") (pin "L3") (pinfunction "~{ACT}_L3") (pintype "input"))
      (node (ref "R47") (pin "2") (pinfunction "2_2") (pintype "passive"))
    )
    (net (code "139") (name "/DDR4_ALERT_B") (class "Default")
      (node (ref "IC13") (pin "P9") (pinfunction "~{ALERT}_P9") (pintype "output"))
      (node (ref "IC14") (pin "P9") (pinfunction "~{ALERT}_P9") (pintype "output"))
      (node (ref "R54") (pin "2") (pinfunction "2_2") (pintype "passive"))
    )
    (net (code "140") (name "/DDR4_BA0") (class "Default")
      (node (ref "IC13") (pin "N2") (pinfunction "BA0_N2") (pintype "input"))
      (node (ref "IC14") (pin "N2") (pinfunction "BA0_N2") (pintype "input"))
      (node (ref "R52") (pin "2") (pinfunction "2_2") (pintype "passive"))
    )
    (net (code "141") (name "/DDR4_BA1") (class "Default")
      (node (ref "IC13") (pin "N8") (pinfunction "BA1_N8") (pintype "input"))
      (node (ref "IC14") (pin "N8") (pinfunction "BA1_N8") (pintype "input"))
      (node (ref "R53") (pin "2") (pinfunction "2_2") (pintype "passive"))
    )
    (net (code "142") (name "/DDR4_BG0") (class "Default")
      (node (ref "IC13") (pin "M2") (pinfunction "BG0_M2") (pintype "input"))
      (node (ref "IC14") (pin "M2") (pinfunction "BG0_M2") (pintype "input"))
      (node (ref "R55") (pin "2") (pinfunction "2_2") (pintype "passive"))
    )
    (net (code "143") (name "/DDR4_CKE") (class "Default")
      (node (ref "IC13") (pin "K2") (pinfunction "CKE_K2") (pintype "input"))
      (node (ref "IC14") (pin "K2") (pinfunction "CKE_K2") (pintype "input"))
      (node (ref "R45") (pin "2") (pinfunction "2_2") (pintype "passive"))
    )
    (net (code "144") (name "/DDR4_CK_C") (class "Default")
      (node (ref "IC13") (pin "K8") (pinfunction "CK_c_K8") (pintype "input"))
      (node (ref "IC14") (pin "K8") (pinfunction "CK_c_K8") (pintype "input"))
      (node (ref "R44") (pin "2") (pinfunction "2_2") (pintype "passive"))
    )
    (net (code "145") (name "/DDR4_CK_T") (class "Default")
      (node (ref "IC13") (pin "K7") (pinfunction "CK_t_K7") (pintype "input"))
      (node (ref "IC14") (pin "K7") (pinfunction "CK_t_K7") (pintype "input"))
      (node (ref "R43") (pin "2") (pinfunction "2_2") (pintype "passive"))
    )
    (net (code "146") (name "/DDR4_CS_B") (class "Default")
      (node (ref "IC13") (pin "L7") (pinfunction "~{CS}_L7") (pintype "input"))
      (node (ref "IC14") (pin "L7") (pinfunction "~{CS}_L7") (pintype "input"))
      (node (ref "R49") (pin "2") (pinfunction "2_2") (pintype "passive"))
    )
    (net (code "147") (name "/DDR4_DM0") (class "Default")
      (node (ref "IC13") (pin "E7") (pinfunction "NF/~{LDM}/~{LDBI}_E7") (pintype "input"))
    )
    (net (code "148") (name "/DDR4_DM1") (class "Default")
      (node (ref "IC13") (pin "E2") (pinfunction "NF/~{UDM}/~{UDBI}_E2") (pintype "input"))
    )
    (net (code "149") (name "/DDR4_DM2") (class "Default")
      (node (ref "IC14") (pin "E7") (pinfunction "NF/~{LDM}/~{LDBI}_E7") (pintype "input"))
    )
    (net (code "150") (name "/DDR4_DM3") (class "Default")
      (node (ref "IC14") (pin "E2") (pinfunction "NF/~{UDM}/~{UDBI}_E2") (pintype "input"))
    )
    (net (code "151") (name "/DDR4_DQ0") (class "Default")
      (node (ref "IC13") (pin "G2") (pinfunction "DQ0_G2") (pintype "bidirectional"))
    )
    (net (code "152") (name "/DDR4_DQ1") (class "Default")
      (node (ref "IC13") (pin "F7") (pinfunction "DQ1_F7") (pintype "bidirectional"))
    )
    (net (code "153") (name "/DDR4_DQ2") (class "Default")
      (node (ref "IC13") (pin "H3") (pinfunction "DQ2_H3") (pintype "bidirectional"))
    )
    (net (code "154") (name "/DDR4_DQ3") (class "Default")
      (node (ref "IC13") (pin "H7") (pinfunction "DQ3_H7") (pintype "bidirectional"))
    )
    (net (code "155") (name "/DDR4_DQ4") (class "Default")
      (node (ref "IC13") (pin "H2") (pinfunction "DQ4_H2") (pintype "bidirectional"))
    )
    (net (code "156") (name "/DDR4_DQ5") (class "Default")
      (node (ref "IC13") (pin "H8") (pinfunction "DQ5_H8") (pintype "bidirectional"))
    )
    (net (code "157") (name "/DDR4_DQ6") (class "Default")
      (node (ref "IC13") (pin "J3") (pinfunction "DQ6_J3") (pintype "bidirectional"))
    )
    (net (code "158") (name "/DDR4_DQ7") (class "Default")
      (node (ref "IC13") (pin "J7") (pinfunction "DQ7_J7") (pintype "bidirectional"))
    )
    (net (code "159") (name "/DDR4_DQ8") (class "Default")
      (node (ref "IC13") (pin "A3") (pinfunction "DQ8_A3") (pintype "bidirectional"))
    )
    (net (code "160") (name "/DDR4_DQ9") (class "Default")
      (node (ref "IC13") (pin "B8") (pinfunction "DQ9_B8") (pintype "bidirectional"))
    )
    (net (code "161") (name "/DDR4_DQ10") (class "Default")
      (node (ref "IC13") (pin "C3") (pinfunction "DQ10_C3") (pintype "bidirectional"))
    )
    (net (code "162") (name "/DDR4_DQ11") (class "Default")
      (node (ref "IC13") (pin "C7") (pinfunction "DQ11_C7") (pintype "bidirectional"))
    )
    (net (code "163") (name "/DDR4_DQ12") (class "Default")
      (node (ref "IC13") (pin "C2") (pinfunction "DQ12_C2") (pintype "bidirectional"))
    )
    (net (code "164") (name "/DDR4_DQ13") (class "Default")
      (node (ref "IC13") (pin "C8") (pinfunction "DQ13_C8") (pintype "bidirectional"))
    )
    (net (code "165") (name "/DDR4_DQ14") (class "Default")
      (node (ref "IC13") (pin "D3") (pinfunction "DQ14_D3") (pintype "bidirectional"))
    )
    (net (code "166") (name "/DDR4_DQ15") (class "Default")
      (node (ref "IC13") (pin "D7") (pinfunction "DQ15_D7") (pintype "bidirectional"))
    )
    (net (code "167") (name "/DDR4_DQ16") (class "Default")
      (node (ref "IC14") (pin "G2") (pinfunction "DQ0_G2") (pintype "bidirectional"))
    )
    (net (code "168") (name "/DDR4_DQ17") (class "Default")
      (node (ref "IC14") (pin "F7") (pinfunction "DQ1_F7") (pintype "bidirectional"))
    )
    (net (code "169") (name "/DDR4_DQ18") (class "Default")
      (node (ref "IC14") (pin "H3") (pinfunction "DQ2_H3") (pintype "bidirectional"))
    )
    (net (code "170") (name "/DDR4_DQ19") (class "Default")
      (node (ref "IC14") (pin "H7") (pinfunction "DQ3_H7") (pintype "bidirectional"))
    )
    (net (code "171") (name "/DDR4_DQ20") (class "Default")
      (node (ref "IC14") (pin "H2") (pinfunction "DQ4_H2") (pintype "bidirectional"))
    )
    (net (code "172") (name "/DDR4_DQ21") (class "Default")
      (node (ref "IC14") (pin "H8") (pinfunction "DQ5_H8") (pintype "bidirectional"))
    )
    (net (code "173") (name "/DDR4_DQ22") (class "Default")
      (node (ref "IC14") (pin "J3") (pinfunction "DQ6_J3") (pintype "bidirectional"))
    )
    (net (code "174") (name "/DDR4_DQ23") (class "Default")
      (node (ref "IC14") (pin "J7") (pinfunction "DQ7_J7") (pintype "bidirectional"))
    )
    (net (code "175") (name "/DDR4_DQ24") (class "Default")
      (node (ref "IC14") (pin "A3") (pinfunction "DQ8_A3") (pintype "bidirectional"))
    )
    (net (code "176") (name "/DDR4_DQ25") (class "Default")
      (node (ref "IC14") (pin "B8") (pinfunction "DQ9_B8") (pintype "bidirectional"))
    )
    (net (code "177") (name "/DDR4_DQ26") (class "Default")
      (node (ref "IC14") (pin "C3") (pinfunction "DQ10_C3") (pintype "bidirectional"))
    )
    (net (code "178") (name "/DDR4_DQ27") (class "Default")
      (node (ref "IC14") (pin "C7") (pinfunction "DQ11_C7") (pintype "bidirectional"))
    )
    (net (code "179") (name "/DDR4_DQ28") (class "Default")
      (node (ref "IC14") (pin "C2") (pinfunction "DQ12_C2") (pintype "bidirectional"))
    )
    (net (code "180") (name "/DDR4_DQ29") (class "Default")
      (node (ref "IC14") (pin "C8") (pinfunction "DQ13_C8") (pintype "bidirectional"))
    )
    (net (code "181") (name "/DDR4_DQ30") (class "Default")
      (node (ref "IC14") (pin "D3") (pinfunction "DQ14_D3") (pintype "bidirectional"))
    )
    (net (code "182") (name "/DDR4_DQ31") (class "Default")
      (node (ref "IC14") (pin "D7") (pinfunction "DQ15_D7") (pintype "bidirectional"))
    )
    (net (code "183") (name "/DDR4_DQS0_C") (class "Default")
      (node (ref "IC13") (pin "F3") (pinfunction "LDQS_c_F3") (pintype "bidirectional"))
    )
    (net (code "184") (name "/DDR4_DQS0_T") (class "Default")
      (node (ref "IC13") (pin "G3") (pinfunction "LDQS_t_G3") (pintype "bidirectional"))
    )
    (net (code "185") (name "/DDR4_DQS1_C") (class "Default")
      (node (ref "IC13") (pin "A7") (pinfunction "UDQS_c_A7") (pintype "bidirectional"))
    )
    (net (code "186") (name "/DDR4_DQS1_T") (class "Default")
      (node (ref "IC13") (pin "B7") (pinfunction "UDQS_t_B7") (pintype "bidirectional"))
    )
    (net (code "187") (name "/DDR4_DQS2_C") (class "Default")
      (node (ref "IC14") (pin "F3") (pinfunction "LDQS_c_F3") (pintype "bidirectional"))
    )
    (net (code "188") (name "/DDR4_DQS2_T") (class "Default")
      (node (ref "IC14") (pin "G3") (pinfunction "LDQS_t_G3") (pintype "bidirectional"))
    )
    (net (code "189") (name "/DDR4_DQS3_C") (class "Default")
      (node (ref "IC14") (pin "A7") (pinfunction "UDQS_c_A7") (pintype "bidirectional"))
    )
    (net (code "190") (name "/DDR4_DQS3_T") (class "Default")
      (node (ref "IC14") (pin "B7") (pinfunction "UDQS_t_B7") (pintype "bidirectional"))
    )
    (net (code "191") (name "/DDR4_ODT") (class "Default")
      (node (ref "IC13") (pin "K3") (pinfunction "ODT_K3") (pintype "input"))
      (node (ref "IC14") (pin "K3") (pinfunction "ODT_K3") (pintype "input"))
      (node (ref "R51") (pin "2") (pinfunction "2_2") (pintype "passive"))
    )
    (net (code "192") (name "/DDR4_PAR") (class "Default")
      (node (ref "IC13") (pin "T3") (pinfunction "PAR_T3") (pintype "input"))
      (node (ref "IC14") (pin "T3") (pinfunction "PAR_T3") (pintype "input"))
      (node (ref "R48") (pin "2") (pinfunction "2_2") (pintype "passive"))
    )
    (net (code "193") (name "/DDR4_RESET_B") (class "Default")
      (node (ref "IC13") (pin "P1") (pinfunction "~{RESET}_P1") (pintype "input"))
      (node (ref "IC14") (pin "P1") (pinfunction "~{RESET}_P1") (pintype "input"))
      (node (ref "R46") (pin "2") (pinfunction "2_2") (pintype "passive"))
    )
    (net (code "194") (name "/DDR4_TEN") (class "Default")
      (node (ref "IC13") (pin "N9") (pinfunction "TEN_N9") (pintype "input"))
      (node (ref "IC14") (pin "N9") (pinfunction "TEN_N9") (pintype "input"))
      (node (ref "R50") (pin "2") (pinfunction "2_2") (pintype "passive"))
    )
    (net (code "195") (name "/DDR4_VREFA") (class "Default")
      (node (ref "C96") (pin "1") (pinfunction "1_1") (pintype "passive"))
      (node (ref "IC13") (pin "M1") (pinfunction "VREFCA_M1") (pintype "power_in"))
      (node (ref "R58") (pin "1") (pinfunction "1_1") (pintype "passive"))
      (node (ref "R59") (pin "2") (pinfunction "2_2") (pintype "passive"))
    )
    (net (code "196") (name "/DDR4_VREFB") (class "Default")
      (node (ref "C30") (pin "1") (pinfunction "1_1") (pintype "passive"))
      (node (ref "IC14") (pin "M1") (pinfunction "VREFCA_M1") (pintype "power_in"))
      (node (ref "R61") (pin "1") (pinfunction "1_1") (pintype "passive"))
      (node (ref "R64") (pin "2") (pinfunction "2_2") (pintype "passive"))
    )
    (net (code "198") (name "/DDR4_ZQB") (class "Default")
      (node (ref "IC14") (pin "F9") (pinfunction "ZQ_F9") (pintype "power_in"))
      (node (ref "R57") (pin "2") (pinfunction "2_2") (pintype "passive"))
    )
    (net (code "199") (name "/PGOOD") (class "Default")
      (node (ref "IC15") (pin "9") (pinfunction "PGOOD_9") (pintype "output"))
      (node (ref "R60") (pin "1") (pinfunction "1_1") (pintype "passive"))
    )
    (net (code "200") (name "/REFIN") (class "Default")
      (node (ref "C36") (pin "2") (pinfunction "2_2") (pintype "passive"))
      (node (ref "IC15") (pin "1") (pinfunction "REFIN_1") (pintype "input"))
      (node (ref "R62") (pin "2") (pinfunction "2_2") (pintype "passive"))
      (node (ref "R65") (pin "2") (pinfunction "2_2") (pintype "passive"))
    )
    (net (code "202") (name "/VOSNS") (class "Default")
      (node (ref "C38") (pin "2") (pinfunction "2_2") (pintype "passive"))
      (node (ref "IC15") (pin "5") (pinfunction "VOSNS_5") (pintype "input"))
      (node (ref "R63") (pin "1") (pinfunction "1_1") (pintype "passive"))
    )
    (net (code "204") (name "GND") (class "Default")
      (node (ref "C27") (pin "2") (pinfunction "2_2") (pintype "passive"))
      (node (ref "C28") (pin "2") (pinfunction "2_2") (pintype "passive"))
      (node (ref "C29") (pin "2") (pinfunction "2_2") (pintype "passive"))
      (node (ref "C30") (pin "2") (pinfunction "2_2") (pintype "passive"))
      (node (ref "C31") (pin "2") (pinfunction "2_2") (pintype "passive"))
      (node (ref "C32") (pin "2") (pinfunction "2_2") (pintype "passive"))
      (node (ref "C33") (pin "1") (pinfunction "1_1") (pintype "passive"))
      (node (ref "C34") (pin "2") (pinfunction "2_2") (pintype "passive"))
      (node (ref "C35") (pin "1") (pinfunction "1_1") (pintype "passive"))
      (node (ref "C36") (pin "1") (pinfunction "1_1") (pintype "passive"))
      (node (ref "C37") (pin "1") (pinfunction "1_1") (pintype "passive"))
      (node (ref "C38") (pin "1") (pinfunction "1_1") (pintype "passive"))
      (node (ref "C39") (pin "2") (pinfunction "2_2") (pintype "passive"))
      (node (ref "C40") (pin "2") (pinfunction "2_2") (pintype "passive"))
      (node (ref "C41") (pin "2") (pinfunction "2_2") (pintype "passive"))
      (node (ref "C42") (pin "2") (pinfunction "2_2") (pintype "passive"))
      (node (ref "C43") (pin "2") (pinfunction "2_2") (pintype "passive"))
      (node (ref "C44") (pin "2") (pinfunction "2_2") (pintype "passive"))
      (node (ref "C45") (pin "2") (pinfunction "2_2") (pintype "passive"))
      (node (ref "C46") (pin "2") (pinfunction "2_2") (pintype "passive"))
      (node (ref "C47") (pin "2") (pinfunction "2_2") (pintype "passive"))
      (node (ref "C48") (pin "2") (pinfunction "2_2") (pintype "passive"))
      (node (ref "C49") (pin "2") (pinfunction "2_2") (pintype "passive"))
      (node (ref "C50") (pin "2") (pinfunction "2_2") (pintype "passive"))
      (node (ref "C51") (pin "2") (pinfunction "2_2") (pintype "passive"))
      (node (ref "C52") (pin "2") (pinfunction "2_2") (pintype "passive"))
      (node (ref "C53") (pin "2") (pinfunction "2_2") (pintype "passive"))
      (node (ref "C54") (pin "2") (pinfunction "2_2") (pintype "passive"))
      (node (ref "C55") (pin "2") (pinfunction "2_2") (pintype "passive"))
      (node (ref "C56") (pin "2") (pinfunction "2_2") (pintype "passive"))
      (node (ref "C57") (pin "2") (pinfunction "2_2") (pintype "passive"))
      (node (ref "C58") (pin "2") (pinfunction "2_2") (pintype "passive"))
      (node (ref "C59") (pin "2") (pinfunction "2_2") (pintype "passive"))
      (node (ref "C60") (pin "2") (pinfunction "2_2") (pintype "passive"))
      (node (ref "C61") (pin "2") (pinfunction "2_2") (pintype "passive"))
      (node (ref "C62") (pin "2") (pinfunction "2_2") (pintype "passive"))
      (node (ref "C63") (pin "2") (pinfunction "2_2") (pintype "passive"))
      (node (ref "C64") (pin "2") (pinfunction "2_2") (pintype "passive"))
      (node (ref "C65") (pin "2") (pinfunction "2_2") (pintype "passive"))
      (node (ref "C66") (pin "2") (pinfunction "2_2") (pintype "passive"))
      (node (ref "C67") (pin "2") (pinfunction "2_2") (pintype "passive"))
      (node (ref "C68") (pin "2") (pinfunction "2_2") (pintype "passive"))
      (node (ref "C69") (pin "2") (pinfunction "2_2") (pintype "passive"))
      (node (ref "C70") (pin "2") (pinfunction "2_2") (pintype "passive"))
      (node (ref "C71") (pin "2") (pinfunction "2_2") (pintype "passive"))
      (node (ref "C72") (pin "2") (pinfunction "2_2") (pintype "passive"))
      (node (ref "C73") (pin "2") (pinfunction "2_2") (pintype "passive"))
      (node (ref "C74") (pin "2") (pinfunction "2_2") (pintype "passive"))
      (node (ref "C75") (pin "2") (pinfunction "2_2") (pintype "passive"))
      (node (ref "C76") (pin "2") (pinfunction "2_2") (pintype "passive"))
      (node (ref "C77") (pin "2") (pinfunction "2_2") (pintype "passive"))
      (node (ref "C78") (pin "2") (pinfunction "2_2") (pintype "passive"))
      (node (ref "C79") (pin "2") (pinfunction "2_2") (pintype "passive"))
      (node (ref "C80") (pin "2") (pinfunction "2_2") (pintype "passive"))
      (node (ref "C81") (pin "2") (pinfunction "2_2") (pintype "passive"))
      (node (ref "C82") (pin "2") (pinfunction "2_2") (pintype "passive"))
      (node (ref "C83") (pin "2") (pinfunction "2_2") (pintype "passive"))
      (node (ref "C84") (pin "2") (pinfunction "2_2") (pintype "passive"))
      (node (ref "C85") (pin "2") (pinfunction "2_2") (pintype "passive"))
      (node (ref "C86") (pin "2") (pinfunction "2_2") (pintype "passive"))
      (node (ref "C87") (pin "2") (pinfunction "2_2") (pintype "passive"))
      (node (ref "C88") (pin "2") (pinfunction "2_2") (pintype "passive"))
      (node (ref "C89") (pin "2") (pinfunction "2_2") (pintype "passive"))
      (node (ref "C90") (pin "2") (pinfunction "2_2") (pintype "passive"))
      (node (ref "C91") (pin "2") (pinfunction "2_2") (pintype "passive"))
      (node (ref "C92") (pin "2") (pinfunction "2_2") (pintype "passive"))
      (node (ref "C93") (pin "1") (pinfunction "1_1") (pintype "passive"))
      (node (ref "C96") (pin "2") (pinfunction "2_2") (pintype "passive"))
      (node (ref "IC13") (pin "A2") (pinfunction "VSSQ_A2") (pintype "power_in"))
      (node (ref "IC13") (pin "A8") (pinfunction "VSSQ_A8") (pintype "power_in"))
      (node (ref "IC13") (pin "B2") (pinfunction "VSS_B2") (pintype "power_in"))
      (node (ref "IC13") (pin "C9") (pinfunction "VSSQ_C9") (pintype "power_in"))
      (node (ref "IC13") (pin "D2") (pinfunction "VSSQ_D2") (pintype "power_in"))
      (node (ref "IC13") (pin "D8") (pinfunction "VSSQ_D8") (pintype "power_in"))
      (node (ref "IC13") (pin "E1") (pinfunction "VSS_E1") (pintype "power_in"))
      (node (ref "IC13") (pin "E3") (pinfunction "VSSQ_E3") (pintype "power_in"))
      (node (ref "IC13") (pin "E8") (pinfunction "VSSQ_E8") (pintype "power_in"))
      (node (ref "IC13") (pin "E9") (pinfunction "VSS_E9") (pintype "power_in"))
      (node (ref "IC13") (pin "F1") (pinfunction "VSSQ_F1") (pintype "power_in"))
      (node (ref "IC13") (pin "G8") (pinfunction "VSS_G8") (pintype "power_in"))
      (node (ref "IC13") (pin "H1") (pinfunction "VSSQ_H1") (pintype "power_in"))
      (node (ref "IC13") (pin "H9") (pinfunction "VSSQ_H9") (pintype "power_in"))
      (node (ref "IC13") (pin "K1") (pinfunction "VSS_K1") (pintype "power_in"))
      (node (ref "IC13") (pin "K9") (pinfunction "VSS_K9") (pintype "power_in"))
      (node (ref "IC13") (pin "M9") (pinfunction "VSS_M9") (pintype "power_in"))
      (node (ref "IC13") (pin "N1") (pinfunction "VSS_N1") (pintype "power_in"))
      (node (ref "IC13") (pin "T1") (pinfunction "VSS_T1") (pintype "power_in"))
      (node (ref "IC14") (pin "A2") (pinfunction "VSSQ_A2") (pintype "power_in"))
      (node (ref "IC14") (pin "A8") (pinfunction "VSSQ_A8") (pintype "power_in"))
      (node (ref "IC14") (pin "B2") (pinfunction "VSS_B2") (pintype "power_in"))
      (node (ref "IC14") (pin "C9") (pinfunction "VSSQ_C9") (pintype "power_in"))
      (node (ref "IC14") (pin "D2") (pinfunction "VSSQ_D2") (pintype "power_in"))
      (node (ref "IC14") (pin "D8") (pinfunction "VSSQ_D8") (pintype "power_in"))
      (node (ref "IC14") (pin "E1") (pinfunction "VSS_E1") (pintype "power_in"))
      (node (ref "IC14") (pin "E3") (pinfunction "VSSQ_E3") (pintype "power_in"))
      (node (ref "IC14") (pin "E8") (pinfunction "VSSQ_E8") (pintype "power_in"))
      (node (ref "IC14") (pin "E9") (pinfunction "VSS_E9") (pintype "power_in"))
      (node (ref "IC14") (pin "F1") (pinfunction "VSSQ_F1") (pintype "power_in"))
      (node (ref "IC14") (pin "G8") (pinfunction "VSS_G8") (pintype "power_in"))
      (node (ref "IC14") (pin "H1") (pinfunction "VSSQ_H1") (pintype "power_in"))
      (node (ref "IC14") (pin "H9") (pinfunction "VSSQ_H9") (pintype "power_in"))
      (node (ref "IC14") (pin "K1") (pinfunction "VSS_K1") (pintype "power_in"))
      (node (ref "IC14") (pin "K9") (pinfunction "VSS_K9") (pintype "power_in"))
      (node (ref "IC14") (pin "M9") (pinfunction "VSS_M9") (pintype "power_in"))
      (node (ref "IC14") (pin "N1") (pinfunction "VSS_N1") (pintype "power_in"))
      (node (ref "IC14") (pin "T1") (pinfunction "VSS_T1") (pintype "power_in"))
      (node (ref "IC15") (pin "11") (pinfunction "EP_11") (pintype "power_in"))
      (node (ref "IC15") (pin "4") (pinfunction "PGND_4") (pintype "power_in"))
      (node (ref "IC15") (pin "8") (pinfunction "GND_8") (pintype "power_in"))
      (node (ref "R46") (pin "1") (pinfunction "1_1") (pintype "passive"))
      (node (ref "R50") (pin "1") (pinfunction "1_1") (pintype "passive"))
      (node (ref "R56") (pin "1") (pinfunction "1_1") (pintype "passive"))
      (node (ref "R57") (pin "1") (pinfunction "1_1") (pintype "passive"))
      (node (ref "R59") (pin "1") (pinfunction "1_1") (pintype "passive"))
      (node (ref "R64") (pin "1") (pinfunction "1_1") (pintype "passive"))
      (node (ref "R65") (pin "1") (pinfunction "1_1") (pintype "passive"))
    )
    (net (code "205") (name "Net-(C95-Pad1)") (class "Default")
      (node (ref "C95") (pin "1") (pinfunction "1_1") (pintype "passive"))
      (node (ref "R43") (pin "1") (pinfunction "1_1") (pintype "passive"))
      (node (ref "R44") (pin "1") (pinfunction "1_1") (pintype "passive"))
    )
    (net (code "206") (name "Net-(IC13-ZQ)") (class "Default")
      (node (ref "IC13") (pin "F9") (pinfunction "ZQ_F9") (pintype "power_in"))
      (node (ref "R56") (pin "2") (pinfunction "2_2") (pintype "passive"))
    )
    (net (code "207") (name "Net-(IC15-REFOUT)") (class "Default")
      (node (ref "C37") (pin "2") (pinfunction "2_2") (pintype "passive"))
      (node (ref "IC15") (pin "6") (pinfunction "REFOUT_6") (pintype "output"))
    )
    (net (code "208") (name "P1V2_DDR") (class "Default")
      (node (ref "C34") (pin "1") (pinfunction "1_1") (pintype "passive"))
      (node (ref "C39") (pin "1") (pinfunction "1_1") (pintype "passive"))
      (node (ref "C40") (pin "1") (pinfunction "1_1") (pintype "passive"))
      (node (ref "C41") (pin "1") (pinfunction "1_1") (pintype "passive"))
      (node (ref "C42") (pin "1") (pinfunction "1_1") (pintype "passive"))
      (node (ref "C43") (pin "1") (pinfunction "1_1") (pintype "passive"))
      (node (ref "C44") (pin "1") (pinfunction "1_1") (pintype "passive"))
      (node (ref "C45") (pin "1") (pinfunction "1_1") (pintype "passive"))
      (node (ref "C46") (pin "1") (pinfunction "1_1") (pintype "passive"))
      (node (ref "C47") (pin "1") (pinfunction "1_1") (pintype "passive"))
      (node (ref "C48") (pin "1") (pinfunction "1_1") (pintype "passive"))
      (node (ref "C49") (pin "1") (pinfunction "1_1") (pintype "passive"))
      (node (ref "C50") (pin "1") (pinfunction "1_1") (pintype "passive"))
      (node (ref "C55") (pin "1") (pinfunction "1_1") (pintype "passive"))
      (node (ref "C56") (pin "1") (pinfunction "1_1") (pintype "passive"))
      (node (ref "C57") (pin "1") (pinfunction "1_1") (pintype "passive"))
      (node (ref "C59") (pin "1") (pinfunction "1_1") (pintype "passive"))
      (node (ref "C60") (pin "1") (pinfunction "1_1") (pintype "passive"))
      (node (ref "C61") (pin "1") (pinfunction "1_1") (pintype "passive"))
      (node (ref "C62") (pin "1") (pinfunction "1_1") (pintype "passive"))
      (node (ref "C63") (pin "1") (pinfunction "1_1") (pintype "passive"))
      (node (ref "C64") (pin "1") (pinfunction "1_1") (pintype "passive"))
      (node (ref "C65") (pin "1") (pinfunction "1_1") (pintype "passive"))
      (node (ref "C66") (pin "1") (pinfunction "1_1") (pintype "passive"))
      (node (ref "C67") (pin "1") (pinfunction "1_1") (pintype "passive"))
      (node (ref "C68") (pin "1") (pinfunction "1_1") (pintype "passive"))
      (node (ref "C69") (pin "1") (pinfunction "1_1") (pintype "passive"))
      (node (ref "C74") (pin "1") (pinfunction "1_1") (pintype "passive"))
      (node (ref "C75") (pin "1") (pinfunction "1_1") (pintype "passive"))
      (node (ref "C76") (pin "1") (pinfunction "1_1") (pintype "passive"))
      (node (ref "C77") (pin "1") (pinfunction "1_1") (pintype "passive"))
      (node (ref "C78") (pin "1") (pinfunction "1_1") (pintype "passive"))
      (node (ref "C79") (pin "1") (pinfunction "1_1") (pintype "passive"))
      (node (ref "C80") (pin "1") (pinfunction "1_1") (pintype "passive"))
      (node (ref "C81") (pin "1") (pinfunction "1_1") (pintype "passive"))
      (node (ref "C82") (pin "1") (pinfunction "1_1") (pintype "passive"))
      (node (ref "C83") (pin "1") (pinfunction "1_1") (pintype "passive"))
      (node (ref "C84") (pin "1") (pinfunction "1_1") (pintype "passive"))
      (node (ref "C85") (pin "1") (pinfunction "1_1") (pintype "passive"))
      (node (ref "C90") (pin "1") (pinfunction "1_1") (pintype "passive"))
      (node (ref "C91") (pin "1") (pinfunction "1_1") (pintype "passive"))
      (node (ref "C92") (pin "1") (pinfunction "1_1") (pintype "passive"))
      (node (ref "C93") (pin "2") (pinfunction "2_2") (pintype "passive"))
      (node (ref "C95") (pin "2") (pinfunction "2_2") (pintype "passive"))
      (node (ref "IC13") (pin "A1") (pinfunction "VDDQ_A1") (pintype "power_in"))
      (node (ref "IC13") (pin "A9") (pinfunction "VDDQ_A9") (pintype "power_in"))
      (node (ref "IC13") (pin "B3") (pinfunction "VDD_B3") (pintype "power_in"))
      (node (ref "IC13") (pin "B9") (pinfunction "VDD_B9") (pintype "power_in"))
      (node (ref "IC13") (pin "C1") (pinfunction "VDDQ_C1") (pintype "power_in"))
      (node (ref "IC13") (pin "D1") (pinfunction "VDD_D1") (pintype "power_in"))
      (node (ref "IC13") (pin "D9") (pinfunction "VDDQ_D9") (pintype "power_in"))
      (node (ref "IC13") (pin "F2") (pinfunction "VDDQ_F2") (pintype "power_in"))
      (node (ref "IC13") (pin "F8") (pinfunction "VDDQ_F8") (pintype "power_in"))
      (node (ref "IC13") (pin "G1") (pinfunction "VDDQ_G1") (pintype "power_in"))
      (node (ref "IC13") (pin "G7") (pinfunction "VDD_G7") (pintype "power_in"))
      (node (ref "IC13") (pin "G9") (pinfunction "VDDQ_G9") (pintype "power_in"))
      (node (ref "IC13") (pin "J1") (pinfunction "VDD_J1") (pintype "power_in"))
      (node (ref "IC13") (pin "J2") (pinfunction "VDDQ_J2") (pintype "power_in"))
      (node (ref "IC13") (pin "J8") (pinfunction "VDDQ_J8") (pintype "power_in"))
      (node (ref "IC13") (pin "J9") (pinfunction "VDD_J9") (pintype "power_in"))
      (node (ref "IC13") (pin "L1") (pinfunction "VDD_L1") (pintype "power_in"))
      (node (ref "IC13") (pin "L9") (pinfunction "VDD_L9") (pintype "power_in"))
      (node (ref "IC13") (pin "R1") (pinfunction "VDD_R1") (pintype "power_in"))
      (node (ref "IC13") (pin "T9") (pinfunction "VDD_T9") (pintype "power_in"))
      (node (ref "IC14") (pin "A1") (pinfunction "VDDQ_A1") (pintype "power_in"))
      (node (ref "IC14") (pin "A9") (pinfunction "VDDQ_A9") (pintype "power_in"))
      (node (ref "IC14") (pin "B3") (pinfunction "VDD_B3") (pintype "power_in"))
      (node (ref "IC14") (pin "B9") (pinfunction "VDD_B9") (pintype "power_in"))
      (node (ref "IC14") (pin "C1") (pinfunction "VDDQ_C1") (pintype "power_in"))
      (node (ref "IC14") (pin "D1") (pinfunction "VDD_D1") (pintype "power_in"))
      (node (ref "IC14") (pin "D9") (pinfunction "VDDQ_D9") (pintype "power_in"))
      (node (ref "IC14") (pin "F2") (pinfunction "VDDQ_F2") (pintype "power_in"))
      (node (ref "IC14") (pin "F8") (pinfunction "VDDQ_F8") (pintype "power_in"))
      (node (ref "IC14") (pin "G1") (pinfunction "VDDQ_G1") (pintype "power_in"))
      (node (ref "IC14") (pin "G7") (pinfunction "VDD_G7") (pintype "power_in"))
      (node (ref "IC14") (pin "G9") (pinfunction "VDDQ_G9") (pintype "power_in"))
      (node (ref "IC14") (pin "J1") (pinfunction "VDD_J1") (pintype "power_in"))
      (node (ref "IC14") (pin "J2") (pinfunction "VDDQ_J2") (pintype "power_in"))
      (node (ref "IC14") (pin "J8") (pinfunction "VDDQ_J8") (pintype "power_in"))
      (node (ref "IC14") (pin "J9") (pinfunction "VDD_J9") (pintype "power_in"))
      (node (ref "IC14") (pin "L1") (pinfunction "VDD_L1") (pintype "power_in"))
      (node (ref "IC14") (pin "L9") (pinfunction "VDD_L9") (pintype "power_in"))
      (node (ref "IC14") (pin "R1") (pinfunction "VDD_R1") (pintype "power_in"))
      (node (ref "IC14") (pin "T9") (pinfunction "VDD_T9") (pintype "power_in"))
      (node (ref "IC15") (pin "2") (pinfunction "VLDOIN_2") (pintype "input"))
      (node (ref "R54") (pin "1") (pinfunction "1_1") (pintype "passive"))
      (node (ref "R58") (pin "2") (pinfunction "2_2") (pintype "passive"))
      (node (ref "R61") (pin "2") (pinfunction "2_2") (pintype "passive"))
      (node (ref "R62") (pin "1") (pinfunction "1_1") (pintype "passive"))
    )
    (net (code "209") (name "P2V5") (class "Default")
      (node (ref "C27") (pin "1") (pinfunction "1_1") (pintype "passive"))
      (node (ref "C28") (pin "1") (pinfunction "1_1") (pintype "passive"))
      (node (ref "C31") (pin "1") (pinfunction "1_1") (pintype "passive"))
      (node (ref "C32") (pin "1") (pinfunction "1_1") (pintype "passive"))
      (node (ref "IC13") (pin "B1") (pinfunction "VPP_B1") (pintype "power_in"))
      (node (ref "IC13") (pin "R9") (pinfunction "VPP_R9") (pintype "power_in"))
      (node (ref "IC14") (pin "B1") (pinfunction "VPP_B1") (pintype "power_in"))
      (node (ref "IC14") (pin "R9") (pinfunction "VPP_R9") (pintype "power_in"))
    )
    (net (code "210") (name "P3V3") (class "Default")
      (node (ref "C29") (pin "1") (pinfunction "1_1") (pintype "passive"))
      (node (ref "IC15") (pin "10") (pinfunction "VIN_10") (pintype "input"))
      (node (ref "IC15") (pin "7") (pinfunction "EN_7") (pintype "input"))
      (node (ref "R60") (pin "2") (pinfunction "2_2") (pintype "passive"))
    )
    (net (code "211") (name "VTT32") (class "Default")
      (node (ref "C33") (pin "2") (pinfunction "2_2") (pintype "passive"))
      (node (ref "C35") (pin "2") (pinfunction "2_2") (pintype "passive"))
      (node (ref "C51") (pin "1") (pinfunction "1_1") (pintype "passive"))
      (node (ref "C52") (pin "1") (pinfunction "1_1") (pintype "passive"))
      (node (ref "C53") (pin "1") (pinfunction "1_1") (pintype "passive"))
      (node (ref "C54") (pin "1") (pinfunction "1_1") (pintype "passive"))
      (node (ref "C58") (pin "1") (pinfunction "1_1") (pintype "passive"))
      (node (ref "C70") (pin "1") (pinfunction "1_1") (pintype "passive"))
      (node (ref "C71") (pin "1") (pinfunction "1_1") (pintype "passive"))
      (node (ref "C72") (pin "1") (pinfunction "1_1") (pintype "passive"))
      (node (ref "C73") (pin "1") (pinfunction "1_1") (pintype "passive"))
      (node (ref "C86") (pin "1") (pinfunction "1_1") (pintype "passive"))
      (node (ref "C87") (pin "1") (pinfunction "1_1") (pintype "passive"))
      (node (ref "C88") (pin "1") (pinfunction "1_1") (pintype "passive"))
      (node (ref "C89") (pin "1") (pinfunction "1_1") (pintype "passive"))
      (node (ref "IC15") (pin "3") (pinfunction "VO_3") (pintype "power_in"))
      (node (ref "R169") (pin "1") (pinfunction "1_1") (pintype "passive"))
      (node (ref "R170") (pin "1") (pinfunction "1_1") (pintype "passive"))
      (node (ref "R28") (pin "1") (pinfunction "1_1") (pintype "passive"))
      (node (ref "R29") (pin "1") (pinfunction "1_1") (pintype "passive"))
      (node (ref "R30") (pin "1") (pinfunction "1_1") (pintype "passive"))
      (node (ref "R31") (pin "1") (pinfunction "1_1") (pintype "passive"))
      (node (ref "R32") (pin "1") (pinfunction "1_1") (pintype "passive"))
      (node (ref "R33") (pin "1") (pinfunction "1_1") (pintype "passive"))
      (node (ref "R34") (pin "1") (pinfunction "1_1") (pintype "passive"))
      (node (ref "R35") (pin "1") (pinfunction "1_1") (pintype "passive"))
      (node (ref "R36") (pin "1") (pinfunction "1_1") (pintype "passive"))
      (node (ref "R37") (pin "1") (pinfunction "1_1") (pintype "passive"))
      (node (ref "R38") (pin "1") (pinfunction "1_1") (pintype "passive"))
      (node (ref "R39") (pin "1") (pinfunction "1_1") (pintype "passive"))
      (node (ref "R40") (pin "1") (pinfunction "1_1") (pintype "passive"))
      (node (ref "R41") (pin "1") (pinfunction "1_1") (pintype "passive"))
      (node (ref "R42") (pin "1") (pinfunction "1_1") (pintype "passive"))
      (node (ref "R45") (pin "1") (pinfunction "1_1") (pintype "passive"))
      (node (ref "R47") (pin "1") (pinfunction "1_1") (pintype "passive"))
      (node (ref "R48") (pin "1") (pinfunction "1_1") (pintype "passive"))
      (node (ref "R49") (pin "1") (pinfunction "1_1") (pintype "passive"))
      (node (ref "R51") (pin "1") (pinfunction "1_1") (pintype "passive"))
      (node (ref "R52") (pin "1") (pinfunction "1_1") (pintype "passive"))
      (node (ref "R53") (pin "1") (pinfunction "1_1") (pintype "passive"))
      (node (ref "R55") (pin "1") (pinfunction "1_1") (pintype "passive"))
      (node (ref "R63") (pin "2") (pinfunction "2_2") (pintype "passive"))
    )
    (net (code "212") (name "unconnected-(IC13-NC-PadT7)") (class "Default")
      (node (ref "IC13") (pin "T7") (pinfunction "NC_T7") (pintype "power_in"))
    )
    (net (code "213") (name "unconnected-(IC14-NC-PadT7)") (class "Default")
      (node (ref "IC14") (pin "T7") (pinfunction "NC_T7") (pintype "power_in"))
    )
  )
)
